# board-scope-R3.net
KiCad netlist of a schematic drawn in EAGLE
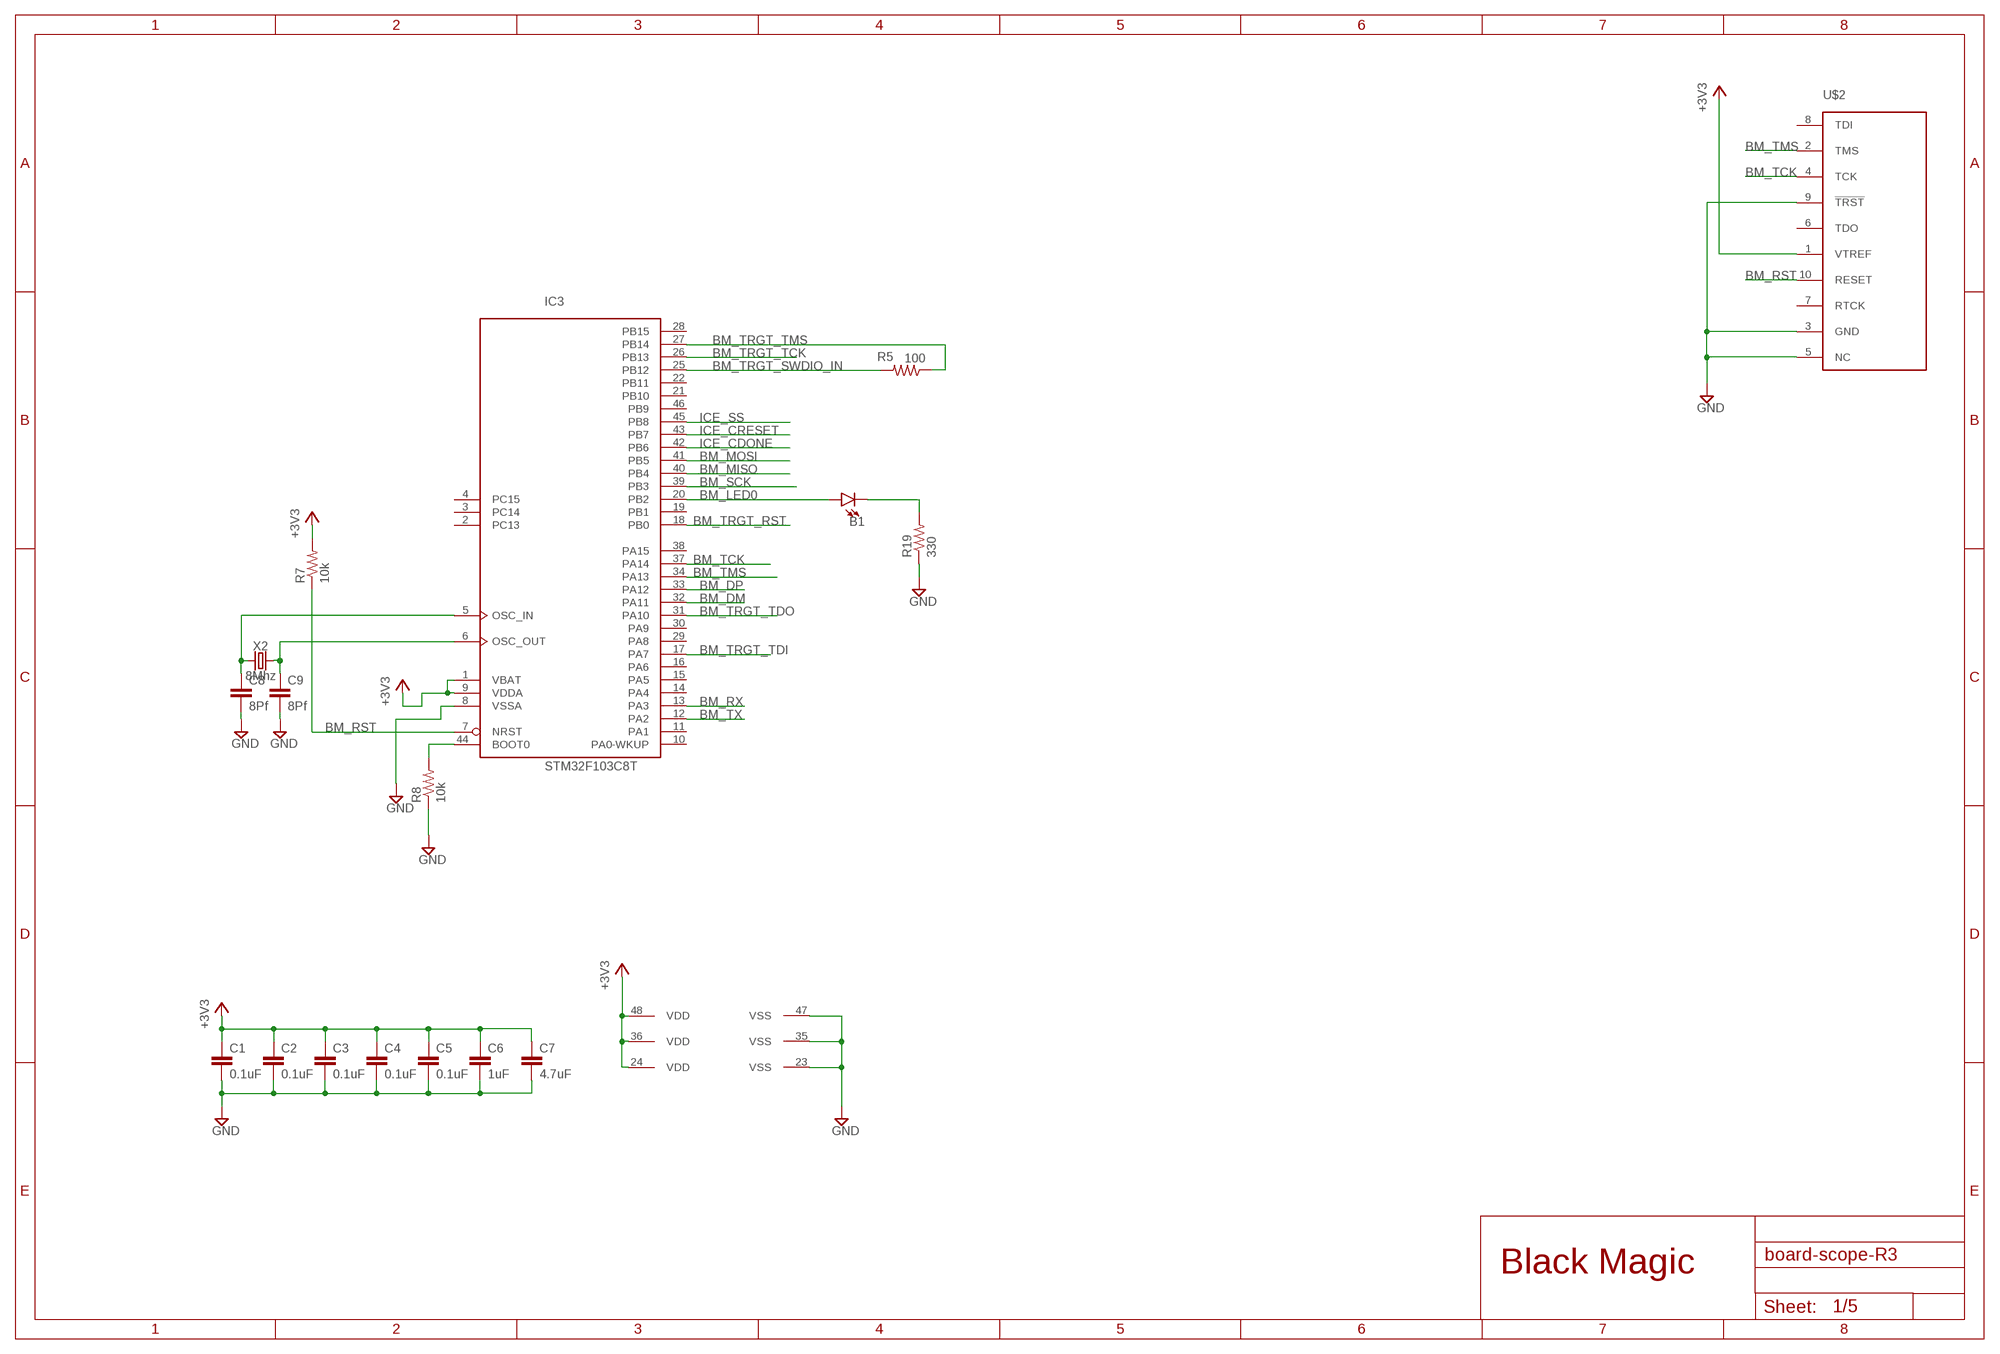
[diagram p0: schematic, sheet 1]
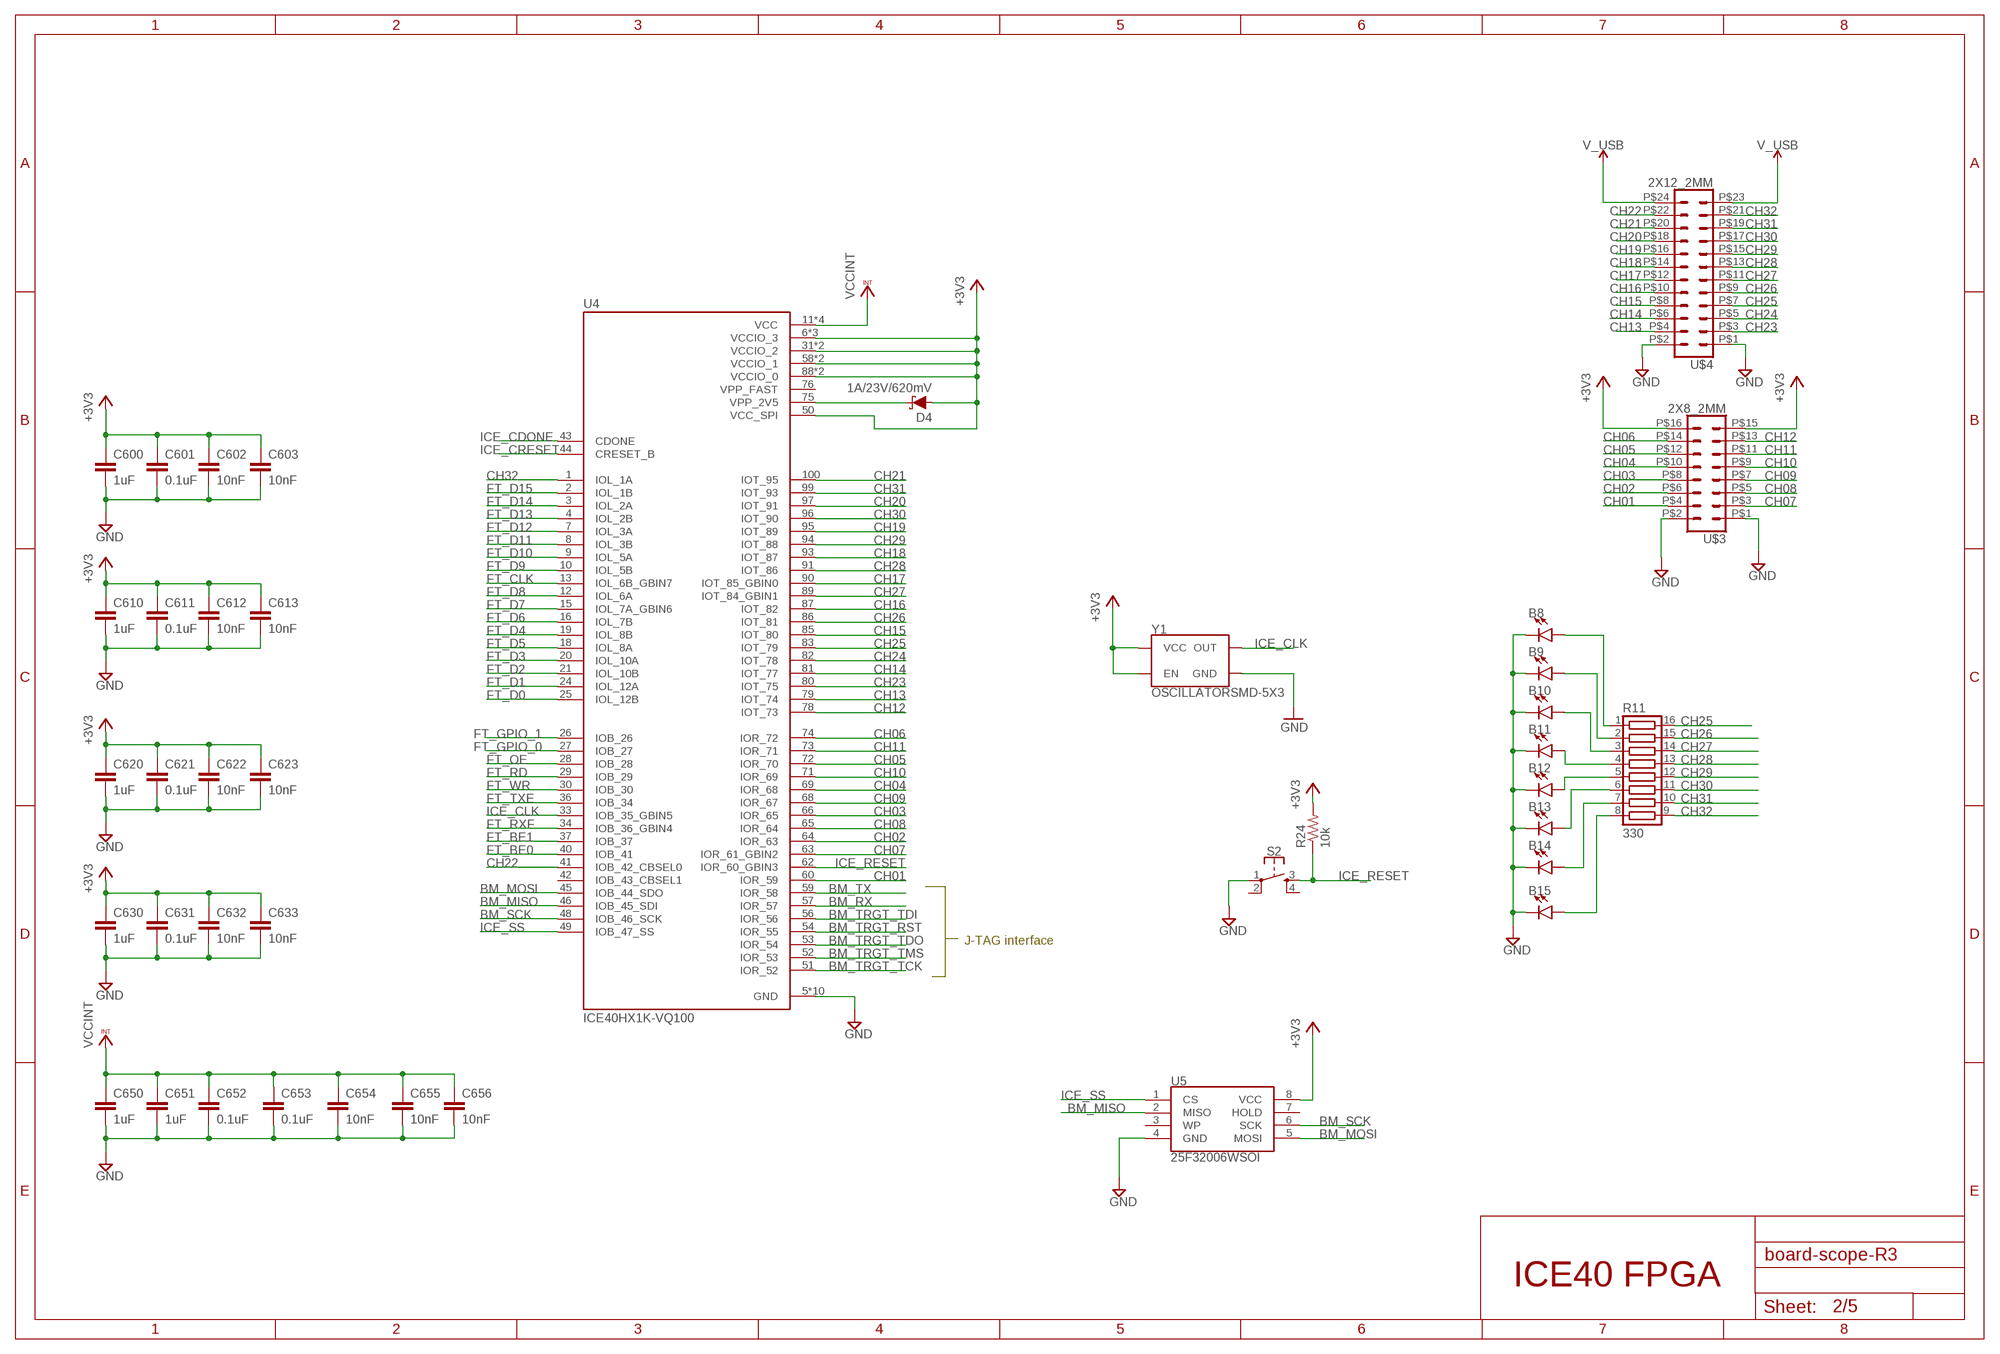
[diagram p1: schematic, sheet 2]
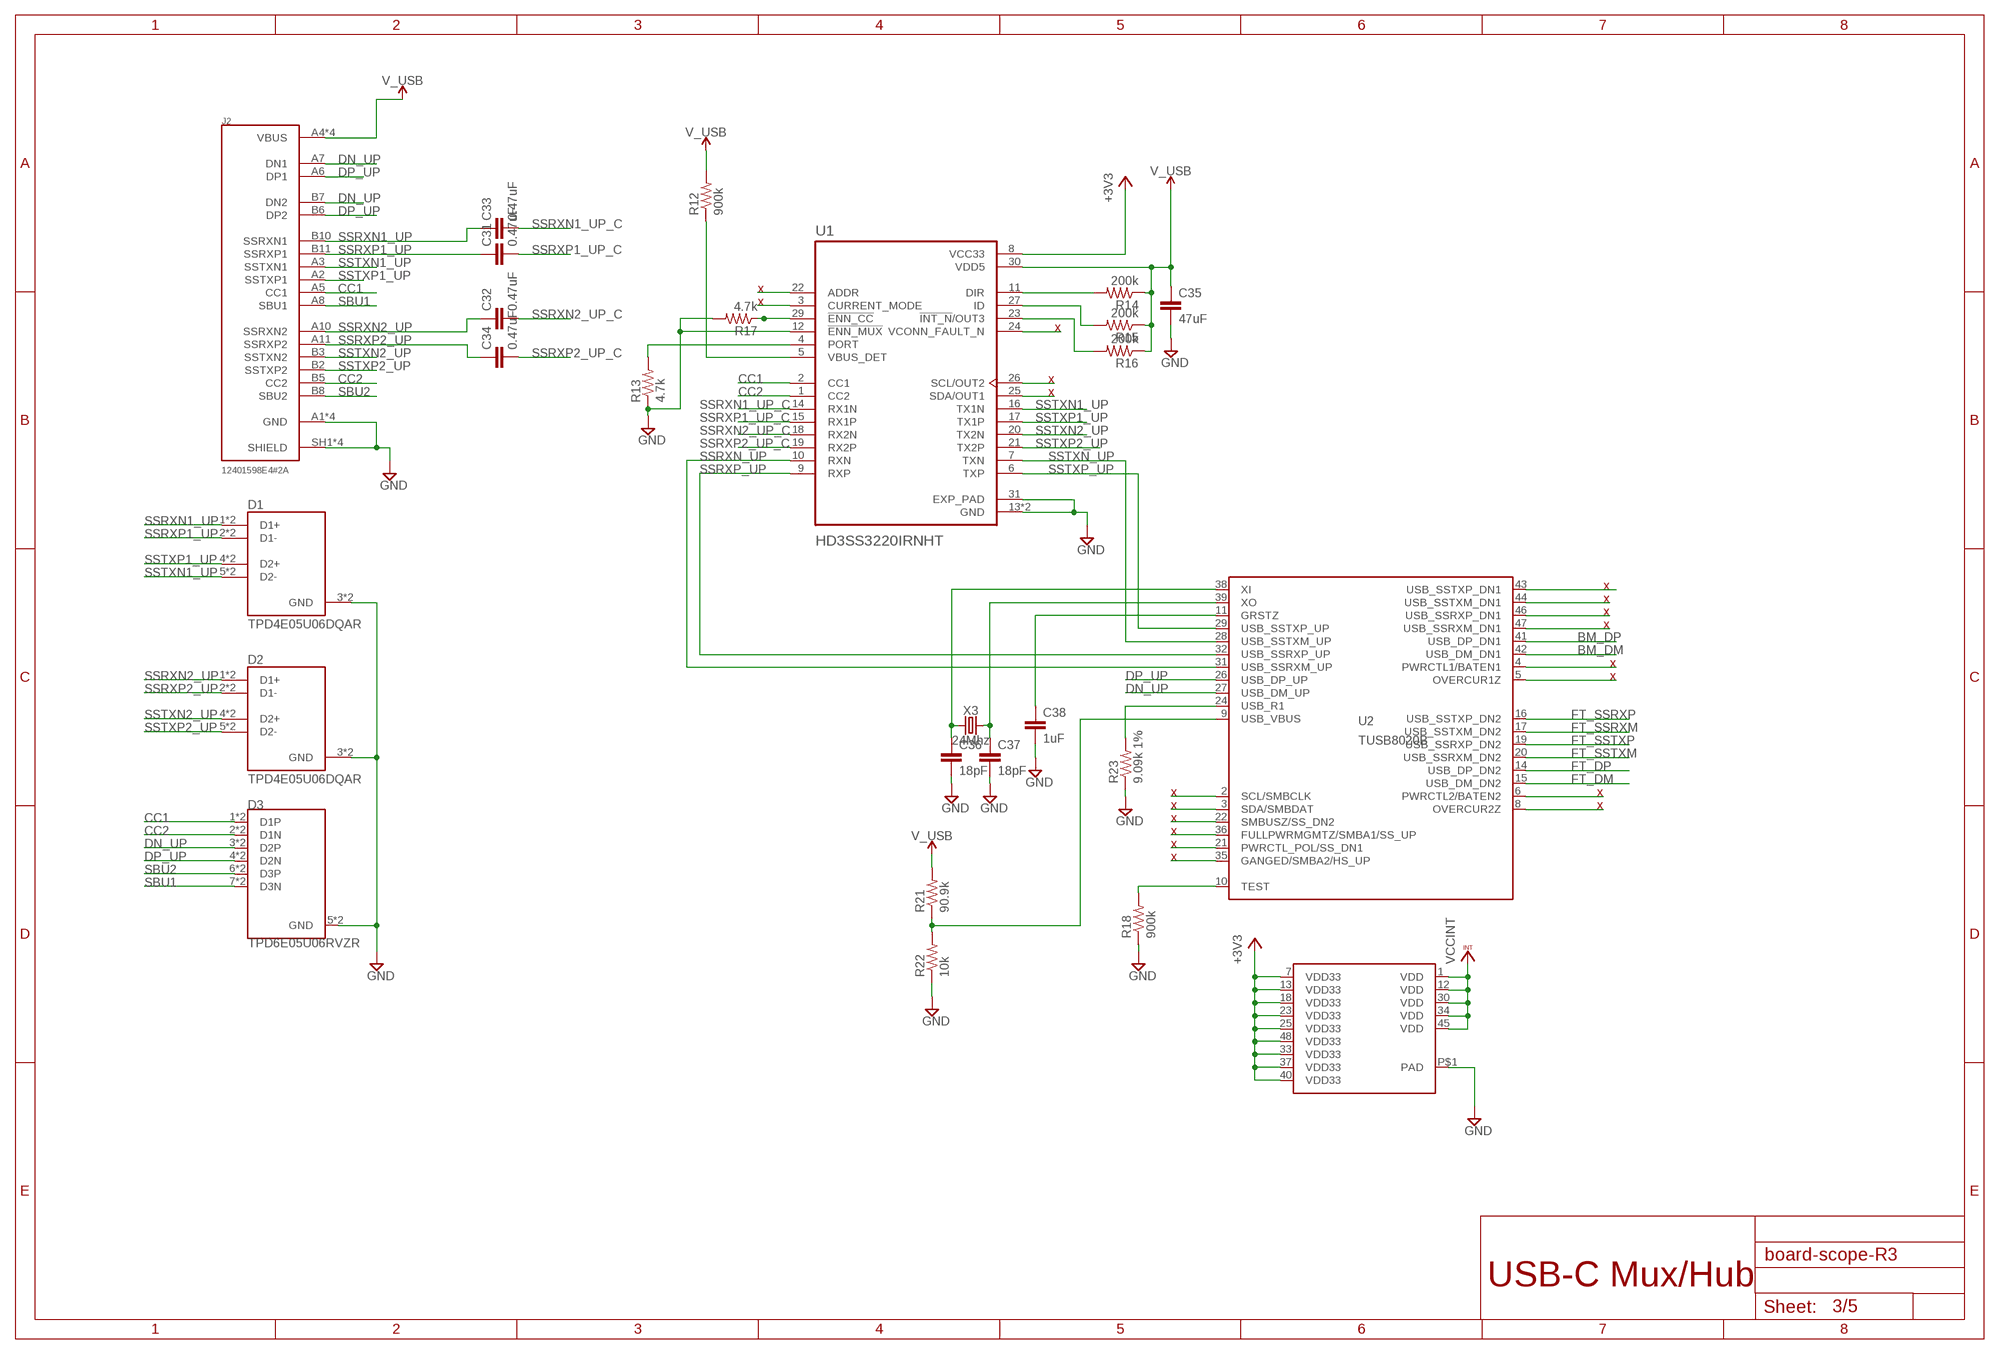
[diagram p2: schematic, sheet 3]
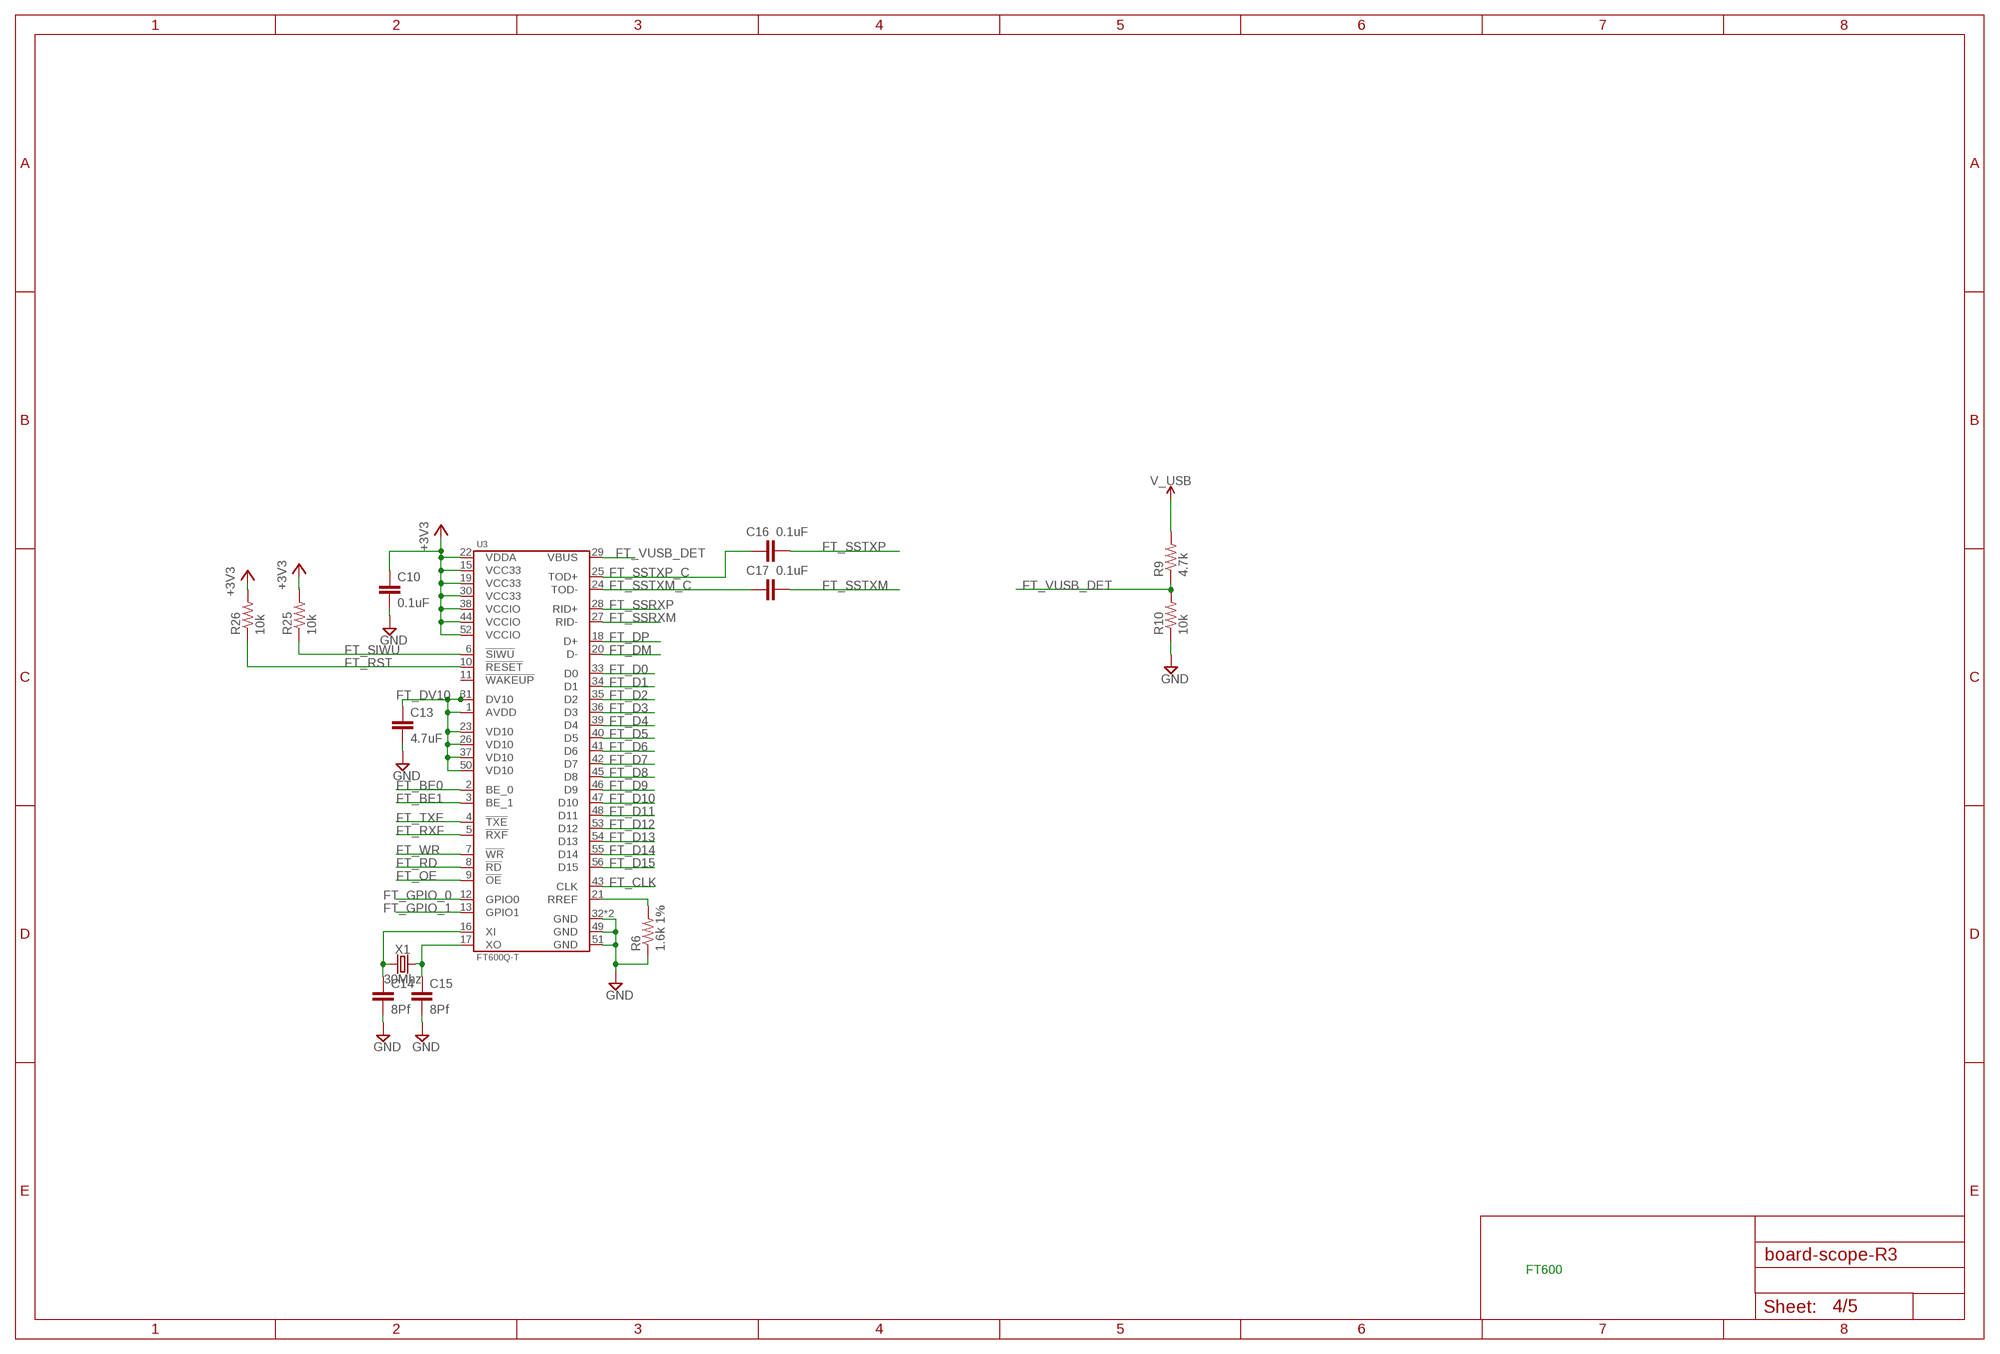
[diagram p3: schematic, sheet 4]
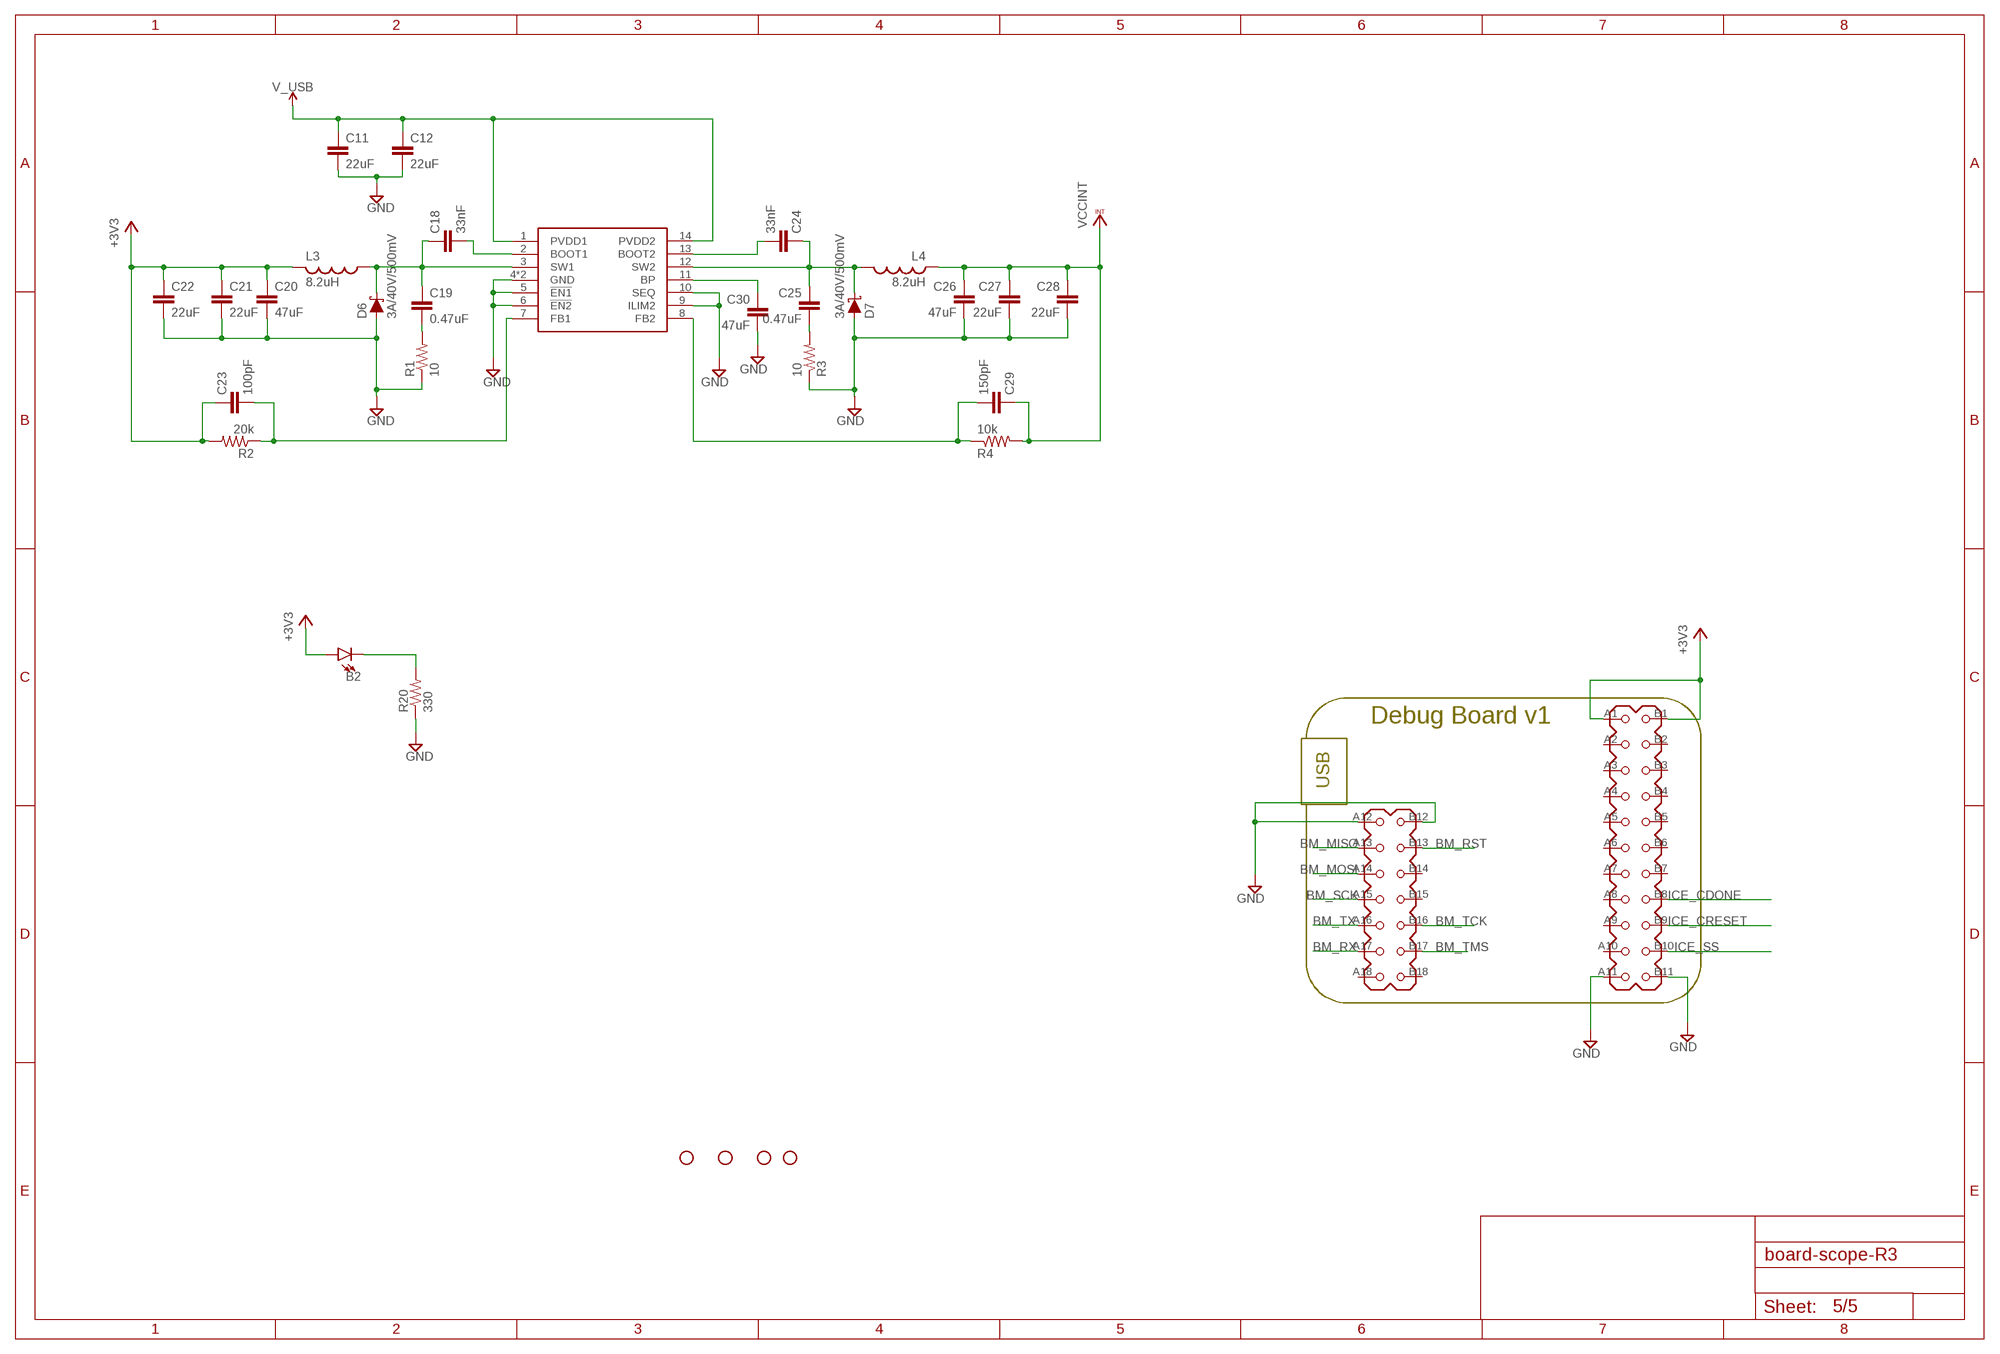
[diagram p4: schematic, sheet 5]

(export (version "E")
  (design (tool "Eeschema 10.0.6"))
  (components
    (comp (ref "C10")
      (value "0.1uF")
      (footprint "eagle-import:C0603K")
      (libsource (lib "eagle-import") (part "C-EUC0603K"))
    )
    (comp (ref "C13")
      (value "4.7uF")
      (footprint "eagle-import:C0603K")
      (libsource (lib "eagle-import") (part "C-EUC0603K"))
    )
    (comp (ref "C14")
      (value "8Pf")
      (footprint "eagle-import:C0603K")
      (libsource (lib "eagle-import") (part "C-EUC0603K"))
    )
    (comp (ref "C15")
      (value "8Pf")
      (footprint "eagle-import:C0603K")
      (libsource (lib "eagle-import") (part "C-EUC0603K"))
    )
    (comp (ref "C16")
      (value "0.1uF")
      (footprint "eagle-import:C0603K")
      (libsource (lib "eagle-import") (part "C-EUC0603K"))
    )
    (comp (ref "C17")
      (value "0.1uF")
      (footprint "eagle-import:C0603K")
      (libsource (lib "eagle-import") (part "C-EUC0603K"))
    )
    (comp (ref "R6")
      (value "1.6k 1%")
      (footprint "eagle-import:R0603")
      (libsource (lib "eagle-import") (part "R-US_R0603"))
    )
    (comp (ref "R9")
      (value "4.7k")
      (footprint "eagle-import:R0603")
      (libsource (lib "eagle-import") (part "R-US_R0603"))
    )
    (comp (ref "R10")
      (value "10k")
      (footprint "eagle-import:R0603")
      (libsource (lib "eagle-import") (part "R-US_R0603"))
    )
    (comp (ref "R25")
      (value "10k")
      (footprint "eagle-import:R0603")
      (libsource (lib "eagle-import") (part "R-US_R0603"))
    )
    (comp (ref "R26")
      (value "10k")
      (footprint "eagle-import:R0603")
      (libsource (lib "eagle-import") (part "R-US_R0603"))
    )
    (comp (ref "U3")
      (value "FT600Q-T")
      (footprint "eagle-import:VQFN-56-7MM")
      (libsource (lib "eagle-import") (part "FT600Q-T"))
    )
    (comp (ref "X1")
      (value "30Mhz")
      (footprint "eagle-import:CRYSTAL-SMD-5X3.2-4PAD")
      (libsource (lib "eagle-import") (part "CRYSTALSMD-5X3.2-4PAD"))
    )
    (comp (ref "B2")
      (value "LED0603")
      (footprint "eagle-import:LED-0603")
      (libsource (lib "eagle-import") (part "LED0603"))
    )
    (comp (ref "C11")
      (value "22uF")
      (footprint "eagle-import:C0603K")
      (libsource (lib "eagle-import") (part "C-EUC0603K"))
    )
    (comp (ref "C12")
      (value "22uF")
      (footprint "eagle-import:C0603K")
      (libsource (lib "eagle-import") (part "C-EUC0603K"))
    )
    (comp (ref "C18")
      (value "33nF")
      (footprint "eagle-import:C0603K")
      (libsource (lib "eagle-import") (part "C-EUC0603K"))
    )
    (comp (ref "C19")
      (value "0.47uF")
      (footprint "eagle-import:C0603K")
      (libsource (lib "eagle-import") (part "C-EUC0603K"))
    )
    (comp (ref "C20")
      (value "47uF")
      (footprint "eagle-import:C0603K")
      (libsource (lib "eagle-import") (part "C-EUC0603K"))
    )
    (comp (ref "C21")
      (value "22uF")
      (footprint "eagle-import:C0603K")
      (libsource (lib "eagle-import") (part "C-EUC0603K"))
    )
    (comp (ref "C22")
      (value "22uF")
      (footprint "eagle-import:C0603K")
      (libsource (lib "eagle-import") (part "C-EUC0603K"))
    )
    (comp (ref "C23")
      (value "100pF")
      (footprint "eagle-import:C0603K")
      (libsource (lib "eagle-import") (part "C-EUC0603K"))
    )
    (comp (ref "C24")
      (value "33nF")
      (footprint "eagle-import:C0603K")
      (libsource (lib "eagle-import") (part "C-EUC0603K"))
    )
    (comp (ref "C25")
      (value "0.47uF")
      (footprint "eagle-import:C0603K")
      (libsource (lib "eagle-import") (part "C-EUC0603K"))
    )
    (comp (ref "C26")
      (value "47uF")
      (footprint "eagle-import:C0603K")
      (libsource (lib "eagle-import") (part "C-EUC0603K"))
    )
    (comp (ref "C27")
      (value "22uF")
      (footprint "eagle-import:C0603K")
      (libsource (lib "eagle-import") (part "C-EUC0603K"))
    )
    (comp (ref "C28")
      (value "22uF")
      (footprint "eagle-import:C0603K")
      (libsource (lib "eagle-import") (part "C-EUC0603K"))
    )
    (comp (ref "C29")
      (value "150pF")
      (footprint "eagle-import:C0603K")
      (libsource (lib "eagle-import") (part "C-EUC0603K"))
    )
    (comp (ref "C30")
      (value "47uF")
      (footprint "eagle-import:C0603K")
      (libsource (lib "eagle-import") (part "C-EUC0603K"))
    )
    (comp (ref "D6")
      (value "3A/40V/500mV")
      (footprint "eagle-import:SMA-DIODE")
      (libsource (lib "eagle-import") (part "DIODE-SCHOTTKY-B340A"))
    )
    (comp (ref "D7")
      (value "3A/40V/500mV")
      (footprint "eagle-import:SMA-DIODE")
      (libsource (lib "eagle-import") (part "DIODE-SCHOTTKY-B340A"))
    )
    (comp (ref "H1")
      (value "STAND-OFF")
      (footprint "eagle-import:STAND-OFF")
      (libsource (lib "eagle-import") (part "STAND-OFF"))
    )
    (comp (ref "H2")
      (value "STAND-OFF")
      (footprint "eagle-import:STAND-OFF")
      (libsource (lib "eagle-import") (part "STAND-OFF"))
    )
    (comp (ref "H3")
      (value "STAND-OFF")
      (footprint "eagle-import:STAND-OFF")
      (libsource (lib "eagle-import") (part "STAND-OFF"))
    )
    (comp (ref "H4")
      (value "STAND-OFF")
      (footprint "eagle-import:STAND-OFF")
      (libsource (lib "eagle-import") (part "STAND-OFF"))
    )
    (comp (ref "L3")
      (value "8.2uH")
      (footprint "eagle-import:L5650M")
      (libsource (lib "eagle-import") (part "L-USL5650M"))
    )
    (comp (ref "L4")
      (value "8.2uH")
      (footprint "eagle-import:L5650M")
      (libsource (lib "eagle-import") (part "L-USL5650M"))
    )
    (comp (ref "R1")
      (value "10")
      (footprint "eagle-import:R0603")
      (libsource (lib "eagle-import") (part "R-US_R0603"))
    )
    (comp (ref "R2")
      (value "20k")
      (footprint "eagle-import:R0603")
      (libsource (lib "eagle-import") (part "R-US_R0603"))
    )
    (comp (ref "R3")
      (value "10")
      (footprint "eagle-import:R0603")
      (libsource (lib "eagle-import") (part "R-US_R0603"))
    )
    (comp (ref "R4")
      (value "10k")
      (footprint "eagle-import:R0603")
      (libsource (lib "eagle-import") (part "R-US_R0603"))
    )
    (comp (ref "R20")
      (value "330")
      (footprint "eagle-import:R0603")
      (libsource (lib "eagle-import") (part "R-US_R0603"))
    )
    (comp (ref "U$1")
      (value "EDGE_DEBUG")
      (footprint "eagle-import:PCI-E_36_EDGE_MID")
      (libsource (lib "eagle-import") (part "EDGE_DEBUG"))
    )
    (comp (ref "U7")
      (value "TPS54386")
      (footprint "eagle-import:HTSSOP14PWP")
      (libsource (lib "eagle-import") (part "TPS54386"))
    )
    (comp (ref "B1")
      (value "LED0603")
      (footprint "eagle-import:LED-0603")
      (libsource (lib "eagle-import") (part "LED0603"))
    )
    (comp (ref "C1")
      (value "0.1uF")
      (footprint "eagle-import:C0603K")
      (libsource (lib "eagle-import") (part "C-EUC0603K"))
    )
    (comp (ref "C2")
      (value "0.1uF")
      (footprint "eagle-import:C0603K")
      (libsource (lib "eagle-import") (part "C-EUC0603K"))
    )
    (comp (ref "C3")
      (value "0.1uF")
      (footprint "eagle-import:C0603K")
      (libsource (lib "eagle-import") (part "C-EUC0603K"))
    )
    (comp (ref "C4")
      (value "0.1uF")
      (footprint "eagle-import:C0603K")
      (libsource (lib "eagle-import") (part "C-EUC0603K"))
    )
    (comp (ref "C5")
      (value "0.1uF")
      (footprint "eagle-import:C0603K")
      (libsource (lib "eagle-import") (part "C-EUC0603K"))
    )
    (comp (ref "C6")
      (value "1uF")
      (footprint "eagle-import:C0603K")
      (libsource (lib "eagle-import") (part "C-EUC0603K"))
    )
    (comp (ref "C7")
      (value "4.7uF")
      (footprint "eagle-import:C0603K")
      (libsource (lib "eagle-import") (part "C-EUC0603K"))
    )
    (comp (ref "C8")
      (value "8Pf")
      (footprint "eagle-import:C0603K")
      (libsource (lib "eagle-import") (part "C-EUC0603K"))
    )
    (comp (ref "C9")
      (value "8Pf")
      (footprint "eagle-import:C0603K")
      (libsource (lib "eagle-import") (part "C-EUC0603K"))
    )
    (comp (ref "IC3")
      (value "STM32F103C8T")
      (footprint "eagle-import:LQFP48")
      (libsource (lib "eagle-import") (part "STM32F103CT8"))
    )
    (comp (ref "R5")
      (value "100")
      (footprint "eagle-import:R0603")
      (libsource (lib "eagle-import") (part "R-US_R0603"))
    )
    (comp (ref "R7")
      (value "10k")
      (footprint "eagle-import:R0603")
      (libsource (lib "eagle-import") (part "R-US_R0603"))
    )
    (comp (ref "R8")
      (value "10k")
      (footprint "eagle-import:R0603")
      (libsource (lib "eagle-import") (part "R-US_R0603"))
    )
    (comp (ref "R19")
      (value "330")
      (footprint "eagle-import:R0603")
      (libsource (lib "eagle-import") (part "R-US_R0603"))
    )
    (comp (ref "U$2")
      (value "TC2050-NL-MCP-NL")
      (footprint "eagle-import:TC2030-MCP-NL")
      (libsource (lib "eagle-import") (part "TC2050-NL-MCP-NL"))
    )
    (comp (ref "X2")
      (value "8Mhz")
      (footprint "eagle-import:CRYSTAL-SMD-5X3.2-4PAD")
      (libsource (lib "eagle-import") (part "CRYSTALSMD-5X3.2-4PAD"))
    )
    (comp (ref "C31")
      (value "0.47uF")
      (footprint "eagle-import:C0603K")
      (libsource (lib "eagle-import") (part "C-EUC0603K"))
    )
    (comp (ref "C32")
      (value "0.47uF")
      (footprint "eagle-import:C0603K")
      (libsource (lib "eagle-import") (part "C-EUC0603K"))
    )
    (comp (ref "C33")
      (value "0.47uF")
      (footprint "eagle-import:C0603K")
      (libsource (lib "eagle-import") (part "C-EUC0603K"))
    )
    (comp (ref "C34")
      (value "0.47uF")
      (footprint "eagle-import:C0603K")
      (libsource (lib "eagle-import") (part "C-EUC0603K"))
    )
    (comp (ref "C35")
      (value "47uF")
      (footprint "eagle-import:C0603K")
      (libsource (lib "eagle-import") (part "C-EUC0603K"))
    )
    (comp (ref "C36")
      (value "18pF")
      (footprint "eagle-import:C0603K")
      (libsource (lib "eagle-import") (part "C-EUC0603K"))
    )
    (comp (ref "C37")
      (value "18pF")
      (footprint "eagle-import:C0603K")
      (libsource (lib "eagle-import") (part "C-EUC0603K"))
    )
    (comp (ref "C38")
      (value "1uF")
      (footprint "eagle-import:C0603K")
      (libsource (lib "eagle-import") (part "C-EUC0603K"))
    )
    (comp (ref "D1")
      (value "TPD4E05U06DQAR")
      (footprint "eagle-import:TI_TPD4E05U06DQAR")
      (fields (field (name "MANUFACTURER") "Texas Instruments"))
      (libsource (lib "eagle-import") (part "TPD4E05U06DQAR"))
    )
    (comp (ref "D2")
      (value "TPD4E05U06DQAR")
      (footprint "eagle-import:TI_TPD4E05U06DQAR")
      (fields (field (name "MANUFACTURER") "Texas Instruments"))
      (libsource (lib "eagle-import") (part "TPD4E05U06DQAR"))
    )
    (comp (ref "D3")
      (value "TPD6E05U06RVZR")
      (footprint "eagle-import:SON50P135X350X55-14N")
      (fields (field (name "MANUFACTURER") "Texas Instruments"))
      (libsource (lib "eagle-import") (part "TPD6E05U06RVZR"))
    )
    (comp (ref "J2")
      (value "12401598E4#2A")
      (footprint "eagle-import:AMPHENOL_12401598E4#2A")
      (fields (field (name "MF") "Amphenol ICC"))
      (libsource (lib "eagle-import") (part "12401598E4#2A"))
    )
    (comp (ref "R12")
      (value "900k")
      (footprint "eagle-import:R0603")
      (libsource (lib "eagle-import") (part "R-US_R0603"))
    )
    (comp (ref "R13")
      (value "4.7k")
      (footprint "eagle-import:R0603")
      (libsource (lib "eagle-import") (part "R-US_R0603"))
    )
    (comp (ref "R14")
      (value "200k")
      (footprint "eagle-import:R0603")
      (libsource (lib "eagle-import") (part "R-US_R0603"))
    )
    (comp (ref "R15")
      (value "200k")
      (footprint "eagle-import:R0603")
      (libsource (lib "eagle-import") (part "R-US_R0603"))
    )
    (comp (ref "R16")
      (value "200k")
      (footprint "eagle-import:R0603")
      (libsource (lib "eagle-import") (part "R-US_R0603"))
    )
    (comp (ref "R17")
      (value "4.7k")
      (footprint "eagle-import:R0603")
      (libsource (lib "eagle-import") (part "R-US_R0603"))
    )
    (comp (ref "R18")
      (value "900k")
      (footprint "eagle-import:R0603")
      (libsource (lib "eagle-import") (part "R-US_R0603"))
    )
    (comp (ref "R21")
      (value "90.9k")
      (footprint "eagle-import:R0603")
      (libsource (lib "eagle-import") (part "R-US_R0603"))
    )
    (comp (ref "R22")
      (value "10k")
      (footprint "eagle-import:R0603")
      (libsource (lib "eagle-import") (part "R-US_R0603"))
    )
    (comp (ref "R23")
      (value "9.09k 1%")
      (footprint "eagle-import:R0603")
      (libsource (lib "eagle-import") (part "R-US_R0603"))
    )
    (comp (ref "U1")
      (value "HD3SS3220IRNHT")
      (footprint "eagle-import:QFN40P450X250X80-31N120X320")
      (fields (field (name "MF") "Texas Instruments"))
      (libsource (lib "eagle-import") (part "HD3SS3220IRNHT"))
    )
    (comp (ref "U2")
      (value "TUSB8020B")
      (footprint "eagle-import:TQFP48")
      (libsource (lib "eagle-import") (part "TUSB8020B"))
    )
    (comp (ref "X3")
      (value "24Mhz")
      (footprint "eagle-import:CRYSTAL-SMD-5X3.2-4PAD")
      (libsource (lib "eagle-import") (part "CRYSTALSMD-5X3.2-4PAD"))
    )
    (comp (ref "B8")
      (value "LED0603")
      (footprint "eagle-import:LED-0603")
      (libsource (lib "eagle-import") (part "LED0603"))
    )
    (comp (ref "B9")
      (value "LED0603")
      (footprint "eagle-import:LED-0603")
      (libsource (lib "eagle-import") (part "LED0603"))
    )
    (comp (ref "B10")
      (value "LED0603")
      (footprint "eagle-import:LED-0603")
      (libsource (lib "eagle-import") (part "LED0603"))
    )
    (comp (ref "B11")
      (value "LED0603")
      (footprint "eagle-import:LED-0603")
      (libsource (lib "eagle-import") (part "LED0603"))
    )
    (comp (ref "B12")
      (value "LED0603")
      (footprint "eagle-import:LED-0603")
      (libsource (lib "eagle-import") (part "LED0603"))
    )
    (comp (ref "B13")
      (value "LED0603")
      (footprint "eagle-import:LED-0603")
      (libsource (lib "eagle-import") (part "LED0603"))
    )
    (comp (ref "B14")
      (value "LED0603")
      (footprint "eagle-import:LED-0603")
      (libsource (lib "eagle-import") (part "LED0603"))
    )
    (comp (ref "B15")
      (value "LED0603")
      (footprint "eagle-import:LED-0603")
      (libsource (lib "eagle-import") (part "LED0603"))
    )
    (comp (ref "C600")
      (value "1uF")
      (footprint "eagle-import:C0603K")
      (libsource (lib "eagle-import") (part "C-EUC0603K"))
    )
    (comp (ref "C601")
      (value "0.1uF")
      (footprint "eagle-import:C0603K")
      (libsource (lib "eagle-import") (part "C-EUC0603K"))
    )
    (comp (ref "C602")
      (value "10nF")
      (footprint "eagle-import:C0603K")
      (libsource (lib "eagle-import") (part "C-EUC0603K"))
    )
    (comp (ref "C603")
      (value "10nF")
      (footprint "eagle-import:C0603K")
      (libsource (lib "eagle-import") (part "C-EUC0603K"))
    )
    (comp (ref "C610")
      (value "1uF")
      (footprint "eagle-import:C0603K")
      (libsource (lib "eagle-import") (part "C-EUC0603K"))
    )
    (comp (ref "C611")
      (value "0.1uF")
      (footprint "eagle-import:C0603K")
      (libsource (lib "eagle-import") (part "C-EUC0603K"))
    )
    (comp (ref "C612")
      (value "10nF")
      (footprint "eagle-import:C0603K")
      (libsource (lib "eagle-import") (part "C-EUC0603K"))
    )
    (comp (ref "C613")
      (value "10nF")
      (footprint "eagle-import:C0603K")
      (libsource (lib "eagle-import") (part "C-EUC0603K"))
    )
    (comp (ref "C620")
      (value "1uF")
      (footprint "eagle-import:C0603K")
      (libsource (lib "eagle-import") (part "C-EUC0603K"))
    )
    (comp (ref "C621")
      (value "0.1uF")
      (footprint "eagle-import:C0603K")
      (libsource (lib "eagle-import") (part "C-EUC0603K"))
    )
    (comp (ref "C622")
      (value "10nF")
      (footprint "eagle-import:C0603K")
      (libsource (lib "eagle-import") (part "C-EUC0603K"))
    )
    (comp (ref "C623")
      (value "10nF")
      (footprint "eagle-import:C0603K")
      (libsource (lib "eagle-import") (part "C-EUC0603K"))
    )
    (comp (ref "C630")
      (value "1uF")
      (footprint "eagle-import:C0603K")
      (libsource (lib "eagle-import") (part "C-EUC0603K"))
    )
    (comp (ref "C631")
      (value "0.1uF")
      (footprint "eagle-import:C0603K")
      (libsource (lib "eagle-import") (part "C-EUC0603K"))
    )
    (comp (ref "C632")
      (value "10nF")
      (footprint "eagle-import:C0603K")
      (libsource (lib "eagle-import") (part "C-EUC0603K"))
    )
    (comp (ref "C633")
      (value "10nF")
      (footprint "eagle-import:C0603K")
      (libsource (lib "eagle-import") (part "C-EUC0603K"))
    )
    (comp (ref "C650")
      (value "1uF")
      (footprint "eagle-import:C0603K")
      (libsource (lib "eagle-import") (part "C-EUC0603K"))
    )
    (comp (ref "C651")
      (value "1uF")
      (footprint "eagle-import:C0603K")
      (libsource (lib "eagle-import") (part "C-EUC0603K"))
    )
    (comp (ref "C652")
      (value "0.1uF")
      (footprint "eagle-import:C0603K")
      (libsource (lib "eagle-import") (part "C-EUC0603K"))
    )
    (comp (ref "C653")
      (value "0.1uF")
      (footprint "eagle-import:C0603K")
      (libsource (lib "eagle-import") (part "C-EUC0603K"))
    )
    (comp (ref "C654")
      (value "10nF")
      (footprint "eagle-import:C0603K")
      (libsource (lib "eagle-import") (part "C-EUC0603K"))
    )
    (comp (ref "C655")
      (value "10nF")
      (footprint "eagle-import:C0603K")
      (libsource (lib "eagle-import") (part "C-EUC0603K"))
    )
    (comp (ref "C656")
      (value "10nF")
      (footprint "eagle-import:C0603K")
      (libsource (lib "eagle-import") (part "C-EUC0603K"))
    )
    (comp (ref "D4")
      (value "1A/23V/620mV")
      (footprint "eagle-import:SOD-323")
      (libsource (lib "eagle-import") (part "DIODE-SCHOTTKY-BAT20J"))
    )
    (comp (ref "R11")
      (value "330")
      (footprint "eagle-import:CTS743C163")
      (libsource (lib "eagle-import") (part "CTS742C163"))
    )
    (comp (ref "R24")
      (value "10k")
      (footprint "eagle-import:R0603")
      (libsource (lib "eagle-import") (part "R-US_R0603"))
    )
    (comp (ref "S2")
      (value "MOMENTARY-SWITCH-SPST-2-SMD-5.2MM")
      (footprint "eagle-import:TACTILE_SWITCH_SMD_5.2MM")
      (libsource (lib "eagle-import") (part "MOMENTARY-SWITCH-SPST-2-SMD-5.2MM"))
    )
    (comp (ref "U$3")
      (value "2X8_2MM")
      (footprint "eagle-import:2X8_2MM")
      (libsource (lib "eagle-import") (part "2X8_2MM"))
    )
    (comp (ref "U$4")
      (value "2X12_2MM")
      (footprint "eagle-import:2X12_2MM")
      (libsource (lib "eagle-import") (part "2X12_2MM"))
    )
    (comp (ref "U4")
      (value "ICE40HX1K-VQ100")
      (footprint "eagle-import:QFP50P1600X1600X120-100N")
      (fields (field (name "MF") "Lattice Semiconductor"))
      (libsource (lib "eagle-import") (part "ICE40HX1K-VQ100"))
    )
    (comp (ref "U5")
      (value "25F32006WSOI")
      (footprint "eagle-import:SO08-EIAJ")
      (libsource (lib "eagle-import") (part "SPI_FLASH-X25XXSMD1"))
    )
    (comp (ref "Y1")
      (value "OSCILLATORSMD-5X3")
      (footprint "eagle-import:OSCILLATOR-SMD-5X3.2")
      (libsource (lib "eagle-import") (part "OSCILLATORSMD-5X3"))
    )
  )
  (nets
    (net (code "1") (name "+3V3") (class "Default")
      (node (ref "B2") (pin "A") (pinfunction "A_A") (pintype "passive"))
      (node (ref "C1") (pin "1") (pinfunction "1_1") (pintype "passive"))
      (node (ref "C10") (pin "1") (pinfunction "1_1") (pintype "passive"))
      (node (ref "C2") (pin "1") (pinfunction "1_1") (pintype "passive"))
      (node (ref "C20") (pin "1") (pinfunction "1_1") (pintype "passive"))
      (node (ref "C21") (pin "1") (pinfunction "1_1") (pintype "passive"))
      (node (ref "C22") (pin "1") (pinfunction "1_1") (pintype "passive"))
      (node (ref "C23") (pin "1") (pinfunction "1_1") (pintype "passive"))
      (node (ref "C3") (pin "1") (pinfunction "1_1") (pintype "passive"))
      (node (ref "C4") (pin "1") (pinfunction "1_1") (pintype "passive"))
      (node (ref "C5") (pin "1") (pinfunction "1_1") (pintype "passive"))
      (node (ref "C6") (pin "1") (pinfunction "1_1") (pintype "passive"))
      (node (ref "C600") (pin "1") (pinfunction "1_1") (pintype "passive"))
      (node (ref "C601") (pin "1") (pinfunction "1_1") (pintype "passive"))
      (node (ref "C602") (pin "1") (pinfunction "1_1") (pintype "passive"))
      (node (ref "C603") (pin "1") (pinfunction "1_1") (pintype "passive"))
      (node (ref "C610") (pin "1") (pinfunction "1_1") (pintype "passive"))
      (node (ref "C611") (pin "1") (pinfunction "1_1") (pintype "passive"))
      (node (ref "C612") (pin "1") (pinfunction "1_1") (pintype "passive"))
      (node (ref "C613") (pin "1") (pinfunction "1_1") (pintype "passive"))
      (node (ref "C620") (pin "1") (pinfunction "1_1") (pintype "passive"))
      (node (ref "C621") (pin "1") (pinfunction "1_1") (pintype "passive"))
      (node (ref "C622") (pin "1") (pinfunction "1_1") (pintype "passive"))
      (node (ref "C623") (pin "1") (pinfunction "1_1") (pintype "passive"))
      (node (ref "C630") (pin "1") (pinfunction "1_1") (pintype "passive"))
      (node (ref "C631") (pin "1") (pinfunction "1_1") (pintype "passive"))
      (node (ref "C632") (pin "1") (pinfunction "1_1") (pintype "passive"))
      (node (ref "C633") (pin "1") (pinfunction "1_1") (pintype "passive"))
      (node (ref "C7") (pin "1") (pinfunction "1_1") (pintype "passive"))
      (node (ref "D4") (pin "A") (pinfunction "A_A") (pintype "passive"))
      (node (ref "IC3") (pin "1") (pinfunction "VBAT_1") (pintype "power_in"))
      (node (ref "IC3") (pin "24") (pinfunction "VDD_24") (pintype "power_in"))
      (node (ref "IC3") (pin "36") (pinfunction "VDD_36") (pintype "power_in"))
      (node (ref "IC3") (pin "48") (pinfunction "VDD_48") (pintype "power_in"))
      (node (ref "IC3") (pin "9") (pinfunction "VDDA_9") (pintype "power_in"))
      (node (ref "L3") (pin "2") (pinfunction "2_2") (pintype "passive"))
      (node (ref "R2") (pin "2") (pinfunction "2_2") (pintype "passive"))
      (node (ref "R24") (pin "2") (pinfunction "2_2") (pintype "passive"))
      (node (ref "R25") (pin "2") (pinfunction "2_2") (pintype "passive"))
      (node (ref "R26") (pin "2") (pinfunction "2_2") (pintype "passive"))
      (node (ref "R7") (pin "2") (pinfunction "2_2") (pintype "passive"))
      (node (ref "U$1") (pin "A1") (pinfunction "A1_A1") (pintype "bidirectional"))
      (node (ref "U$1") (pin "B1") (pinfunction "B1_B1") (pintype "bidirectional"))
      (node (ref "U$2") (pin "1") (pinfunction "VTREF_1") (pintype "bidirectional"))
      (node (ref "U$3") (pin "P$15") (pinfunction "15_P$15") (pintype "passive"))
      (node (ref "U$3") (pin "P$16") (pinfunction "16_P$16") (pintype "passive"))
      (node (ref "U1") (pin "8") (pinfunction "VCC33_8") (pintype "power_in"))
      (node (ref "U2") (pin "13") (pinfunction "VDD33_13") (pintype "bidirectional"))
      (node (ref "U2") (pin "18") (pinfunction "VDD33_18") (pintype "bidirectional"))
      (node (ref "U2") (pin "23") (pinfunction "VDD33_23") (pintype "bidirectional"))
      (node (ref "U2") (pin "25") (pinfunction "VDD33_25") (pintype "bidirectional"))
      (node (ref "U2") (pin "33") (pinfunction "VDD33_33") (pintype "bidirectional"))
      (node (ref "U2") (pin "37") (pinfunction "VDD33_37") (pintype "bidirectional"))
      (node (ref "U2") (pin "40") (pinfunction "VDD33_40") (pintype "bidirectional"))
      (node (ref "U2") (pin "48") (pinfunction "VDD33_48") (pintype "bidirectional"))
      (node (ref "U2") (pin "7") (pinfunction "VDD33_7") (pintype "power_in"))
      (node (ref "U3") (pin "15") (pinfunction "VCC33_15") (pintype "bidirectional"))
      (node (ref "U3") (pin "19") (pinfunction "VCC33_19") (pintype "bidirectional"))
      (node (ref "U3") (pin "22") (pinfunction "VDDA_22") (pintype "bidirectional"))
      (node (ref "U3") (pin "30") (pinfunction "VCC33_30") (pintype "bidirectional"))
      (node (ref "U3") (pin "38") (pinfunction "VCCIO_38") (pintype "bidirectional"))
      (node (ref "U3") (pin "44") (pinfunction "VCCIO_44") (pintype "bidirectional"))
      (node (ref "U3") (pin "52") (pinfunction "VCCIO_52") (pintype "bidirectional"))
      (node (ref "U4") (pin "14") (pinfunction "VCCIO_3_14") (pintype "power_in"))
      (node (ref "U4") (pin "22") (pinfunction "VCCIO_3_22") (pintype "power_in"))
      (node (ref "U4") (pin "31") (pinfunction "VCCIO_2_31") (pintype "power_in"))
      (node (ref "U4") (pin "38") (pinfunction "VCCIO_2_38") (pintype "power_in"))
      (node (ref "U4") (pin "50") (pinfunction "VCC_SPI_50") (pintype "power_in"))
      (node (ref "U4") (pin "58") (pinfunction "VCCIO_1_58") (pintype "power_in"))
      (node (ref "U4") (pin "6") (pinfunction "VCCIO_3_6") (pintype "power_in"))
      (node (ref "U4") (pin "67") (pinfunction "VCCIO_1_67") (pintype "power_in"))
      (node (ref "U4") (pin "88") (pinfunction "VCCIO_0_88") (pintype "power_in"))
      (node (ref "U4") (pin "92") (pinfunction "VCCIO_0_92") (pintype "power_in"))
      (node (ref "U5") (pin "8") (pinfunction "VCC_8") (pintype "power_in"))
      (node (ref "Y1") (pin "1") (pinfunction "EN_1") (pintype "bidirectional"))
      (node (ref "Y1") (pin "4") (pinfunction "VCC_4") (pintype "bidirectional"))
    )
    (net (code "2") (name "BM_DM") (class "Default")
      (node (ref "IC3") (pin "32") (pinfunction "PA11_32") (pintype "bidirectional"))
      (node (ref "U2") (pin "42") (pinfunction "USB_DM_DN1_42") (pintype "bidirectional"))
    )
    (net (code "3") (name "BM_DP") (class "Default")
      (node (ref "IC3") (pin "33") (pinfunction "PA12_33") (pintype "bidirectional"))
      (node (ref "U2") (pin "41") (pinfunction "USB_DP_DN1_41") (pintype "bidirectional"))
    )
    (net (code "4") (name "BM_LED0") (class "Default")
      (node (ref "B1") (pin "A") (pinfunction "A_A") (pintype "passive"))
      (node (ref "IC3") (pin "20") (pinfunction "PB2_20") (pintype "bidirectional"))
    )
    (net (code "5") (name "BM_MISO") (class "Default")
      (node (ref "IC3") (pin "40") (pinfunction "PB4_40") (pintype "bidirectional"))
      (node (ref "U$1") (pin "A13") (pinfunction "A13_A13") (pintype "bidirectional"))
      (node (ref "U4") (pin "46") (pinfunction "IOB_45_SDI_46") (pintype "bidirectional"))
      (node (ref "U5") (pin "2") (pinfunction "MISO_2") (pintype "bidirectional"))
    )
    (net (code "6") (name "BM_MOSI") (class "Default")
      (node (ref "IC3") (pin "41") (pinfunction "PB5_41") (pintype "bidirectional"))
      (node (ref "U$1") (pin "A14") (pinfunction "A14_A14") (pintype "bidirectional"))
      (node (ref "U4") (pin "45") (pinfunction "IOB_44_SDO_45") (pintype "bidirectional"))
      (node (ref "U5") (pin "5") (pinfunction "MOSI_5") (pintype "bidirectional"))
    )
    (net (code "7") (name "BM_RST") (class "Default")
      (node (ref "IC3") (pin "7") (pinfunction "NRST_7") (pintype "bidirectional"))
      (node (ref "R7") (pin "1") (pinfunction "1_1") (pintype "passive"))
      (node (ref "U$1") (pin "B13") (pinfunction "B13_B13") (pintype "bidirectional"))
      (node (ref "U$2") (pin "10") (pinfunction "RESET_10") (pintype "bidirectional"))
    )
    (net (code "8") (name "BM_RX") (class "Default")
      (node (ref "IC3") (pin "13") (pinfunction "PA3_13") (pintype "bidirectional"))
      (node (ref "U$1") (pin "A17") (pinfunction "A17_A17") (pintype "bidirectional"))
      (node (ref "U4") (pin "57") (pinfunction "IOR_57_57") (pintype "bidirectional"))
    )
    (net (code "9") (name "BM_SCK") (class "Default")
      (node (ref "IC3") (pin "39") (pinfunction "PB3_39") (pintype "bidirectional"))
      (node (ref "U$1") (pin "A15") (pinfunction "A15_A15") (pintype "bidirectional"))
      (node (ref "U4") (pin "48") (pinfunction "IOB_46_SCK_48") (pintype "bidirectional"))
      (node (ref "U5") (pin "6") (pinfunction "SCK_6") (pintype "bidirectional"))
    )
    (net (code "10") (name "BM_TCK") (class "Default")
      (node (ref "IC3") (pin "37") (pinfunction "PA14_37") (pintype "bidirectional"))
      (node (ref "U$1") (pin "B16") (pinfunction "B16_B16") (pintype "bidirectional"))
      (node (ref "U$2") (pin "4") (pinfunction "TCK_4") (pintype "bidirectional"))
    )
    (net (code "11") (name "BM_TMS") (class "Default")
      (node (ref "IC3") (pin "34") (pinfunction "PA13_34") (pintype "bidirectional"))
      (node (ref "U$1") (pin "B17") (pinfunction "B17_B17") (pintype "bidirectional"))
      (node (ref "U$2") (pin "2") (pinfunction "TMS_2") (pintype "bidirectional"))
    )
    (net (code "12") (name "BM_TRGT_RST") (class "Default")
      (node (ref "IC3") (pin "18") (pinfunction "PB0_18") (pintype "bidirectional"))
      (node (ref "U4") (pin "54") (pinfunction "IOR_55_54") (pintype "bidirectional"))
    )
    (net (code "13") (name "BM_TRGT_SWDIO_IN") (class "Default")
      (node (ref "IC3") (pin "25") (pinfunction "PB12_25") (pintype "bidirectional"))
      (node (ref "R5") (pin "2") (pinfunction "2_2") (pintype "passive"))
    )
    (net (code "14") (name "BM_TRGT_TCK") (class "Default")
      (node (ref "IC3") (pin "26") (pinfunction "PB13_26") (pintype "bidirectional"))
      (node (ref "U4") (pin "51") (pinfunction "IOR_52_51") (pintype "bidirectional"))
    )
    (net (code "15") (name "BM_TRGT_TDI") (class "Default")
      (node (ref "IC3") (pin "17") (pinfunction "PA7_17") (pintype "bidirectional"))
      (node (ref "U4") (pin "56") (pinfunction "IOR_56_56") (pintype "bidirectional"))
    )
    (net (code "16") (name "BM_TRGT_TDO") (class "Default")
      (node (ref "IC3") (pin "31") (pinfunction "PA10_31") (pintype "bidirectional"))
      (node (ref "U4") (pin "53") (pinfunction "IOR_54_53") (pintype "bidirectional"))
    )
    (net (code "17") (name "BM_TRGT_TMS") (class "Default")
      (node (ref "IC3") (pin "27") (pinfunction "PB14_27") (pintype "bidirectional"))
      (node (ref "R5") (pin "1") (pinfunction "1_1") (pintype "passive"))
      (node (ref "U4") (pin "52") (pinfunction "IOR_53_52") (pintype "bidirectional"))
    )
    (net (code "18") (name "BM_TX") (class "Default")
      (node (ref "IC3") (pin "12") (pinfunction "PA2_12") (pintype "bidirectional"))
      (node (ref "U$1") (pin "A16") (pinfunction "A16_A16") (pintype "bidirectional"))
      (node (ref "U4") (pin "59") (pinfunction "IOR_58_59") (pintype "bidirectional"))
    )
    (net (code "19") (name "CC1") (class "Default")
      (node (ref "D3") (pin "1") (pinfunction "D1P_1") (pintype "bidirectional"))
      (node (ref "D3") (pin "14") (pinfunction "D1P_14") (pintype "bidirectional"))
      (node (ref "J2") (pin "A5") (pinfunction "CC1_A5") (pintype "passive"))
      (node (ref "U1") (pin "2") (pinfunction "CC1_2") (pintype "bidirectional"))
    )
    (net (code "20") (name "CC2") (class "Default")
      (node (ref "D3") (pin "13") (pinfunction "D1N_13") (pintype "bidirectional"))
      (node (ref "D3") (pin "2") (pinfunction "D1N_2") (pintype "bidirectional"))
      (node (ref "J2") (pin "B5") (pinfunction "CC2_B5") (pintype "passive"))
      (node (ref "U1") (pin "1") (pinfunction "CC2_1") (pintype "bidirectional"))
    )
    (net (code "21") (name "CH01") (class "Default")
      (node (ref "U$3") (pin "P$4") (pinfunction "4_P$4") (pintype "passive"))
      (node (ref "U4") (pin "60") (pinfunction "IOR_59_60") (pintype "bidirectional"))
    )
    (net (code "22") (name "CH02") (class "Default")
      (node (ref "U$3") (pin "P$6") (pinfunction "6_P$6") (pintype "passive"))
      (node (ref "U4") (pin "64") (pinfunction "IOR_63_64") (pintype "bidirectional"))
    )
    (net (code "23") (name "CH03") (class "Default")
      (node (ref "U$3") (pin "P$8") (pinfunction "8_P$8") (pintype "passive"))
      (node (ref "U4") (pin "66") (pinfunction "IOR_65_66") (pintype "bidirectional"))
    )
    (net (code "24") (name "CH04") (class "Default")
      (node (ref "U$3") (pin "P$10") (pinfunction "10_P$10") (pintype "passive"))
      (node (ref "U4") (pin "69") (pinfunction "IOR_68_69") (pintype "bidirectional"))
    )
    (net (code "25") (name "CH05") (class "Default")
      (node (ref "U$3") (pin "P$12") (pinfunction "12_P$12") (pintype "passive"))
      (node (ref "U4") (pin "72") (pinfunction "IOR_70_72") (pintype "bidirectional"))
    )
    (net (code "26") (name "CH06") (class "Default")
      (node (ref "U$3") (pin "P$14") (pinfunction "14_P$14") (pintype "passive"))
      (node (ref "U4") (pin "74") (pinfunction "IOR_72_74") (pintype "bidirectional"))
    )
    (net (code "27") (name "CH07") (class "Default")
      (node (ref "U$3") (pin "P$3") (pinfunction "3_P$3") (pintype "passive"))
      (node (ref "U4") (pin "63") (pinfunction "IOR_61_GBIN2_63") (pintype "bidirectional"))
    )
    (net (code "28") (name "CH08") (class "Default")
      (node (ref "U$3") (pin "P$5") (pinfunction "5_P$5") (pintype "passive"))
      (node (ref "U4") (pin "65") (pinfunction "IOR_64_65") (pintype "bidirectional"))
    )
    (net (code "29") (name "CH09") (class "Default")
      (node (ref "U$3") (pin "P$7") (pinfunction "7_P$7") (pintype "passive"))
      (node (ref "U4") (pin "68") (pinfunction "IOR_67_68") (pintype "bidirectional"))
    )
    (net (code "30") (name "CH10") (class "Default")
      (node (ref "U$3") (pin "P$9") (pinfunction "9_P$9") (pintype "passive"))
      (node (ref "U4") (pin "71") (pinfunction "IOR_69_71") (pintype "bidirectional"))
    )
    (net (code "31") (name "CH11") (class "Default")
      (node (ref "U$3") (pin "P$11") (pinfunction "11_P$11") (pintype "passive"))
      (node (ref "U4") (pin "73") (pinfunction "IOR_71_73") (pintype "bidirectional"))
    )
    (net (code "32") (name "CH12") (class "Default")
      (node (ref "U$3") (pin "P$13") (pinfunction "13_P$13") (pintype "passive"))
      (node (ref "U4") (pin "78") (pinfunction "IOT_73_78") (pintype "bidirectional"))
    )
    (net (code "33") (name "CH13") (class "Default")
      (node (ref "U$4") (pin "P$4") (pinfunction "4_P$4") (pintype "passive"))
      (node (ref "U4") (pin "79") (pinfunction "IOT_74_79") (pintype "bidirectional"))
    )
    (net (code "34") (name "CH14") (class "Default")
      (node (ref "U$4") (pin "P$6") (pinfunction "6_P$6") (pintype "passive"))
      (node (ref "U4") (pin "81") (pinfunction "IOT_77_81") (pintype "bidirectional"))
    )
    (net (code "35") (name "CH15") (class "Default")
      (node (ref "U$4") (pin "P$8") (pinfunction "8_P$8") (pintype "passive"))
      (node (ref "U4") (pin "85") (pinfunction "IOT_80_85") (pintype "bidirectional"))
    )
    (net (code "36") (name "CH16") (class "Default")
      (node (ref "U$4") (pin "P$10") (pinfunction "10_P$10") (pintype "passive"))
      (node (ref "U4") (pin "87") (pinfunction "IOT_82_87") (pintype "bidirectional"))
    )
    (net (code "37") (name "CH17") (class "Default")
      (node (ref "U$4") (pin "P$12") (pinfunction "12_P$12") (pintype "passive"))
      (node (ref "U4") (pin "90") (pinfunction "IOT_85_GBIN0_90") (pintype "bidirectional"))
    )
    (net (code "38") (name "CH18") (class "Default")
      (node (ref "U$4") (pin "P$14") (pinfunction "14_P$14") (pintype "passive"))
      (node (ref "U4") (pin "93") (pinfunction "IOT_87_93") (pintype "bidirectional"))
    )
    (net (code "39") (name "CH19") (class "Default")
      (node (ref "U$4") (pin "P$16") (pinfunction "16_P$16") (pintype "passive"))
      (node (ref "U4") (pin "95") (pinfunction "IOT_89_95") (pintype "bidirectional"))
    )
    (net (code "40") (name "CH20") (class "Default")
      (node (ref "U$4") (pin "P$18") (pinfunction "18_P$18") (pintype "passive"))
      (node (ref "U4") (pin "97") (pinfunction "IOT_91_97") (pintype "bidirectional"))
    )
    (net (code "41") (name "CH21") (class "Default")
      (node (ref "U$4") (pin "P$20") (pinfunction "20_P$20") (pintype "passive"))
      (node (ref "U4") (pin "100") (pinfunction "IOT_95_100") (pintype "bidirectional"))
    )
    (net (code "42") (name "CH22") (class "Default")
      (node (ref "U$4") (pin "P$22") (pinfunction "22_P$22") (pintype "passive"))
      (node (ref "U4") (pin "41") (pinfunction "IOB_42_CBSEL0_41") (pintype "bidirectional"))
    )
    (net (code "43") (name "CH23") (class "Default")
      (node (ref "U$4") (pin "P$3") (pinfunction "3_P$3") (pintype "passive"))
      (node (ref "U4") (pin "80") (pinfunction "IOT_75_80") (pintype "bidirectional"))
    )
    (net (code "44") (name "CH24") (class "Default")
      (node (ref "U$4") (pin "P$5") (pinfunction "5_P$5") (pintype "passive"))
      (node (ref "U4") (pin "82") (pinfunction "IOT_78_82") (pintype "bidirectional"))
    )
    (net (code "45") (name "CH25") (class "Default")
      (node (ref "R11") (pin "16") (pinfunction "16_16") (pintype "passive"))
      (node (ref "U$4") (pin "P$7") (pinfunction "7_P$7") (pintype "passive"))
      (node (ref "U4") (pin "83") (pinfunction "IOT_79_83") (pintype "bidirectional"))
    )
    (net (code "46") (name "CH26") (class "Default")
      (node (ref "R11") (pin "15") (pinfunction "15_15") (pintype "passive"))
      (node (ref "U$4") (pin "P$9") (pinfunction "9_P$9") (pintype "passive"))
      (node (ref "U4") (pin "86") (pinfunction "IOT_81_86") (pintype "bidirectional"))
    )
    (net (code "47") (name "CH27") (class "Default")
      (node (ref "R11") (pin "14") (pinfunction "14_14") (pintype "passive"))
      (node (ref "U$4") (pin "P$11") (pinfunction "11_P$11") (pintype "passive"))
      (node (ref "U4") (pin "89") (pinfunction "IOT_84_GBIN1_89") (pintype "bidirectional"))
    )
    (net (code "48") (name "CH28") (class "Default")
      (node (ref "R11") (pin "13") (pinfunction "13_13") (pintype "passive"))
      (node (ref "U$4") (pin "P$13") (pinfunction "13_P$13") (pintype "passive"))
      (node (ref "U4") (pin "91") (pinfunction "IOT_86_91") (pintype "bidirectional"))
    )
    (net (code "49") (name "CH29") (class "Default")
      (node (ref "R11") (pin "12") (pinfunction "12_12") (pintype "passive"))
      (node (ref "U$4") (pin "P$15") (pinfunction "15_P$15") (pintype "passive"))
      (node (ref "U4") (pin "94") (pinfunction "IOT_88_94") (pintype "bidirectional"))
    )
    (net (code "50") (name "CH30") (class "Default")
      (node (ref "R11") (pin "11") (pinfunction "11_11") (pintype "passive"))
      (node (ref "U$4") (pin "P$17") (pinfunction "17_P$17") (pintype "passive"))
      (node (ref "U4") (pin "96") (pinfunction "IOT_90_96") (pintype "bidirectional"))
    )
    (net (code "51") (name "CH31") (class "Default")
      (node (ref "R11") (pin "10") (pinfunction "10_10") (pintype "passive"))
      (node (ref "U$4") (pin "P$19") (pinfunction "19_P$19") (pintype "passive"))
      (node (ref "U4") (pin "99") (pinfunction "IOT_93_99") (pintype "bidirectional"))
    )
    (net (code "52") (name "CH32") (class "Default")
      (node (ref "R11") (pin "9") (pinfunction "9_9") (pintype "passive"))
      (node (ref "U$4") (pin "P$21") (pinfunction "21_P$21") (pintype "passive"))
      (node (ref "U4") (pin "1") (pinfunction "IOL_1A_1") (pintype "bidirectional"))
    )
    (net (code "53") (name "DN_UP") (class "Default")
      (node (ref "D3") (pin "12") (pinfunction "D2P_12") (pintype "bidirectional"))
      (node (ref "D3") (pin "3") (pinfunction "D2P_3") (pintype "bidirectional"))
      (node (ref "J2") (pin "A7") (pinfunction "DN1_A7") (pintype "passive"))
      (node (ref "J2") (pin "B7") (pinfunction "DN2_B7") (pintype "passive"))
      (node (ref "U2") (pin "27") (pinfunction "USB_DM_UP_27") (pintype "bidirectional"))
    )
    (net (code "54") (name "DP_UP") (class "Default")
      (node (ref "D3") (pin "11") (pinfunction "D2N_11") (pintype "bidirectional"))
      (node (ref "D3") (pin "4") (pinfunction "D2N_4") (pintype "bidirectional"))
      (node (ref "J2") (pin "A6") (pinfunction "DP1_A6") (pintype "passive"))
      (node (ref "J2") (pin "B6") (pinfunction "DP2_B6") (pintype "passive"))
      (node (ref "U2") (pin "26") (pinfunction "USB_DP_UP_26") (pintype "bidirectional"))
    )
    (net (code "55") (name "FT_BE0") (class "Default")
      (node (ref "U3") (pin "2") (pinfunction "BE_0_2") (pintype "bidirectional"))
      (node (ref "U4") (pin "40") (pinfunction "IOB_41_40") (pintype "bidirectional"))
    )
    (net (code "56") (name "FT_BE1") (class "Default")
      (node (ref "U3") (pin "3") (pinfunction "BE_1_3") (pintype "bidirectional"))
      (node (ref "U4") (pin "37") (pinfunction "IOB_37_37") (pintype "bidirectional"))
    )
    (net (code "57") (name "FT_CLK") (class "Default")
      (node (ref "U3") (pin "43") (pinfunction "CLK_43") (pintype "bidirectional"))
      (node (ref "U4") (pin "13") (pinfunction "IOL_6B_GBIN7_13") (pintype "bidirectional"))
    )
    (net (code "58") (name "FT_D0") (class "Default")
      (node (ref "U3") (pin "33") (pinfunction "D0_33") (pintype "bidirectional"))
      (node (ref "U4") (pin "25") (pinfunction "IOL_12B_25") (pintype "bidirectional"))
    )
    (net (code "59") (name "FT_D1") (class "Default")
      (node (ref "U3") (pin "34") (pinfunction "D1_34") (pintype "bidirectional"))
      (node (ref "U4") (pin "24") (pinfunction "IOL_12A_24") (pintype "bidirectional"))
    )
    (net (code "60") (name "FT_D2") (class "Default")
      (node (ref "U3") (pin "35") (pinfunction "D2_35") (pintype "bidirectional"))
      (node (ref "U4") (pin "21") (pinfunction "IOL_10B_21") (pintype "bidirectional"))
    )
    (net (code "61") (name "FT_D3") (class "Default")
      (node (ref "U3") (pin "36") (pinfunction "D3_36") (pintype "bidirectional"))
      (node (ref "U4") (pin "20") (pinfunction "IOL_10A_20") (pintype "bidirectional"))
    )
    (net (code "62") (name "FT_D4") (class "Default")
      (node (ref "U3") (pin "39") (pinfunction "D4_39") (pintype "bidirectional"))
      (node (ref "U4") (pin "19") (pinfunction "IOL_8B_19") (pintype "bidirectional"))
    )
    (net (code "63") (name "FT_D5") (class "Default")
      (node (ref "U3") (pin "40") (pinfunction "D5_40") (pintype "bidirectional"))
      (node (ref "U4") (pin "18") (pinfunction "IOL_8A_18") (pintype "bidirectional"))
    )
    (net (code "64") (name "FT_D6") (class "Default")
      (node (ref "U3") (pin "41") (pinfunction "D6_41") (pintype "bidirectional"))
      (node (ref "U4") (pin "16") (pinfunction "IOL_7B_16") (pintype "bidirectional"))
    )
    (net (code "65") (name "FT_D7") (class "Default")
      (node (ref "U3") (pin "42") (pinfunction "D7_42") (pintype "bidirectional"))
      (node (ref "U4") (pin "15") (pinfunction "IOL_7A_GBIN6_15") (pintype "bidirectional"))
    )
    (net (code "66") (name "FT_D8") (class "Default")
      (node (ref "U3") (pin "45") (pinfunction "D8_45") (pintype "bidirectional"))
      (node (ref "U4") (pin "12") (pinfunction "IOL_6A_12") (pintype "bidirectional"))
    )
    (net (code "67") (name "FT_D9") (class "Default")
      (node (ref "U3") (pin "46") (pinfunction "D9_46") (pintype "bidirectional"))
      (node (ref "U4") (pin "10") (pinfunction "IOL_5B_10") (pintype "bidirectional"))
    )
    (net (code "68") (name "FT_D10") (class "Default")
      (node (ref "U3") (pin "47") (pinfunction "D10_47") (pintype "bidirectional"))
      (node (ref "U4") (pin "9") (pinfunction "IOL_5A_9") (pintype "bidirectional"))
    )
    (net (code "69") (name "FT_D11") (class "Default")
      (node (ref "U3") (pin "48") (pinfunction "D11_48") (pintype "bidirectional"))
      (node (ref "U4") (pin "8") (pinfunction "IOL_3B_8") (pintype "bidirectional"))
    )
    (net (code "70") (name "FT_D12") (class "Default")
      (node (ref "U3") (pin "53") (pinfunction "D12_53") (pintype "bidirectional"))
      (node (ref "U4") (pin "7") (pinfunction "IOL_3A_7") (pintype "bidirectional"))
    )
    (net (code "71") (name "FT_D13") (class "Default")
      (node (ref "U3") (pin "54") (pinfunction "D13_54") (pintype "bidirectional"))
      (node (ref "U4") (pin "4") (pinfunction "IOL_2B_4") (pintype "bidirectional"))
    )
    (net (code "72") (name "FT_D14") (class "Default")
      (node (ref "U3") (pin "55") (pinfunction "D14_55") (pintype "bidirectional"))
      (node (ref "U4") (pin "3") (pinfunction "IOL_2A_3") (pintype "bidirectional"))
    )
    (net (code "73") (name "FT_D15") (class "Default")
      (node (ref "U3") (pin "56") (pinfunction "D15_56") (pintype "bidirectional"))
      (node (ref "U4") (pin "2") (pinfunction "IOL_1B_2") (pintype "bidirectional"))
    )
    (net (code "74") (name "FT_DM") (class "Default")
      (node (ref "U2") (pin "15") (pinfunction "USB_DM_DN2_15") (pintype "bidirectional"))
      (node (ref "U3") (pin "20") (pinfunction "D-_20") (pintype "bidirectional"))
    )
    (net (code "75") (name "FT_DP") (class "Default")
      (node (ref "U2") (pin "14") (pinfunction "USB_DP_DN2_14") (pintype "bidirectional"))
      (node (ref "U3") (pin "18") (pinfunction "D+_18") (pintype "bidirectional"))
    )
    (net (code "76") (name "FT_DV10") (class "Default")
      (node (ref "C13") (pin "1") (pinfunction "1_1") (pintype "passive"))
      (node (ref "U3") (pin "1") (pinfunction "AVDD_1") (pintype "bidirectional"))
      (node (ref "U3") (pin "23") (pinfunction "VD10_23") (pintype "bidirectional"))
      (node (ref "U3") (pin "26") (pinfunction "VD10_26") (pintype "bidirectional"))
      (node (ref "U3") (pin "31") (pinfunction "DV10_31") (pintype "bidirectional"))
      (node (ref "U3") (pin "37") (pinfunction "VD10_37") (pintype "bidirectional"))
      (node (ref "U3") (pin "50") (pinfunction "VD10_50") (pintype "bidirectional"))
    )
    (net (code "77") (name "FT_GPIO_0") (class "Default")
      (node (ref "U3") (pin "12") (pinfunction "GPIO0_12") (pintype "bidirectional"))
      (node (ref "U4") (pin "27") (pinfunction "IOB_27_27") (pintype "bidirectional"))
    )
    (net (code "78") (name "FT_GPIO_1") (class "Default")
      (node (ref "U3") (pin "13") (pinfunction "GPIO1_13") (pintype "bidirectional"))
      (node (ref "U4") (pin "26") (pinfunction "IOB_26_26") (pintype "bidirectional"))
    )
    (net (code "79") (name "FT_OE") (class "Default")
      (node (ref "U3") (pin "9") (pinfunction "~{OE}_9") (pintype "bidirectional"))
      (node (ref "U4") (pin "28") (pinfunction "IOB_28_28") (pintype "bidirectional"))
    )
    (net (code "80") (name "FT_RD") (class "Default")
      (node (ref "U3") (pin "8") (pinfunction "~{RD}_8") (pintype "bidirectional"))
      (node (ref "U4") (pin "29") (pinfunction "IOB_29_29") (pintype "bidirectional"))
    )
    (net (code "81") (name "FT_RST") (class "Default")
      (node (ref "R26") (pin "1") (pinfunction "1_1") (pintype "passive"))
      (node (ref "U3") (pin "10") (pinfunction "~{RESET}_10") (pintype "bidirectional"))
    )
    (net (code "82") (name "FT_RXF") (class "Default")
      (node (ref "U3") (pin "5") (pinfunction "~{RXF}_5") (pintype "bidirectional"))
      (node (ref "U4") (pin "34") (pinfunction "IOB_36_GBIN4_34") (pintype "bidirectional"))
    )
    (net (code "83") (name "FT_SIWU") (class "Default")
      (node (ref "R25") (pin "1") (pinfunction "1_1") (pintype "passive"))
      (node (ref "U3") (pin "6") (pinfunction "~{SIWU}_6") (pintype "bidirectional"))
    )
    (net (code "84") (name "FT_SSRXM") (class "Default")
      (node (ref "U2") (pin "17") (pinfunction "USB_SSTXM_DN2_17") (pintype "bidirectional"))
      (node (ref "U3") (pin "27") (pinfunction "RID-_27") (pintype "bidirectional"))
    )
    (net (code "85") (name "FT_SSRXP") (class "Default")
      (node (ref "U2") (pin "16") (pinfunction "USB_SSTXP_DN2_16") (pintype "bidirectional"))
      (node (ref "U3") (pin "28") (pinfunction "RID+_28") (pintype "bidirectional"))
    )
    (net (code "86") (name "FT_SSTXM") (class "Default")
      (node (ref "C17") (pin "2") (pinfunction "2_2") (pintype "passive"))
      (node (ref "U2") (pin "20") (pinfunction "USB_SSRXM_DN2_20") (pintype "bidirectional"))
    )
    (net (code "87") (name "FT_SSTXM_C") (class "Default")
      (node (ref "C17") (pin "1") (pinfunction "1_1") (pintype "passive"))
      (node (ref "U3") (pin "24") (pinfunction "TOD-_24") (pintype "bidirectional"))
    )
    (net (code "88") (name "FT_SSTXP") (class "Default")
      (node (ref "C16") (pin "2") (pinfunction "2_2") (pintype "passive"))
      (node (ref "U2") (pin "19") (pinfunction "USB_SSRXP_DN2_19") (pintype "bidirectional"))
    )
    (net (code "89") (name "FT_SSTXP_C") (class "Default")
      (node (ref "C16") (pin "1") (pinfunction "1_1") (pintype "passive"))
      (node (ref "U3") (pin "25") (pinfunction "TOD+_25") (pintype "bidirectional"))
    )
    (net (code "90") (name "FT_TXE") (class "Default")
      (node (ref "U3") (pin "4") (pinfunction "~{TXE}_4") (pintype "bidirectional"))
      (node (ref "U4") (pin "36") (pinfunction "IOB_34_36") (pintype "bidirectional"))
    )
    (net (code "91") (name "FT_VUSB_DET") (class "Default")
      (node (ref "R10") (pin "2") (pinfunction "2_2") (pintype "passive"))
      (node (ref "R9") (pin "1") (pinfunction "1_1") (pintype "passive"))
      (node (ref "U3") (pin "29") (pinfunction "VBUS_29") (pintype "bidirectional"))
    )
    (net (code "92") (name "FT_WR") (class "Default")
      (node (ref "U3") (pin "7") (pinfunction "~{WR}_7") (pintype "bidirectional"))
      (node (ref "U4") (pin "30") (pinfunction "IOB_30_30") (pintype "bidirectional"))
    )
    (net (code "93") (name "GND") (class "Default")
      (node (ref "B10") (pin "C") (pinfunction "C_C") (pintype "passive"))
      (node (ref "B11") (pin "C") (pinfunction "C_C") (pintype "passive"))
      (node (ref "B12") (pin "C") (pinfunction "C_C") (pintype "passive"))
      (node (ref "B13") (pin "C") (pinfunction "C_C") (pintype "passive"))
      (node (ref "B14") (pin "C") (pinfunction "C_C") (pintype "passive"))
      (node (ref "B15") (pin "C") (pinfunction "C_C") (pintype "passive"))
      (node (ref "B8") (pin "C") (pinfunction "C_C") (pintype "passive"))
      (node (ref "B9") (pin "C") (pinfunction "C_C") (pintype "passive"))
      (node (ref "C1") (pin "2") (pinfunction "2_2") (pintype "passive"))
      (node (ref "C10") (pin "2") (pinfunction "2_2") (pintype "passive"))
      (node (ref "C11") (pin "2") (pinfunction "2_2") (pintype "passive"))
      (node (ref "C12") (pin "2") (pinfunction "2_2") (pintype "passive"))
      (node (ref "C13") (pin "2") (pinfunction "2_2") (pintype "passive"))
      (node (ref "C14") (pin "2") (pinfunction "2_2") (pintype "passive"))
      (node (ref "C15") (pin "2") (pinfunction "2_2") (pintype "passive"))
      (node (ref "C2") (pin "2") (pinfunction "2_2") (pintype "passive"))
      (node (ref "C20") (pin "2") (pinfunction "2_2") (pintype "passive"))
      (node (ref "C21") (pin "2") (pinfunction "2_2") (pintype "passive"))
      (node (ref "C22") (pin "2") (pinfunction "2_2") (pintype "passive"))
      (node (ref "C26") (pin "2") (pinfunction "2_2") (pintype "passive"))
      (node (ref "C27") (pin "2") (pinfunction "2_2") (pintype "passive"))
      (node (ref "C28") (pin "2") (pinfunction "2_2") (pintype "passive"))
      (node (ref "C3") (pin "2") (pinfunction "2_2") (pintype "passive"))
      (node (ref "C30") (pin "2") (pinfunction "2_2") (pintype "passive"))
      (node (ref "C35") (pin "2") (pinfunction "2_2") (pintype "passive"))
      (node (ref "C36") (pin "2") (pinfunction "2_2") (pintype "passive"))
      (node (ref "C37") (pin "2") (pinfunction "2_2") (pintype "passive"))
      (node (ref "C38") (pin "2") (pinfunction "2_2") (pintype "passive"))
      (node (ref "C4") (pin "2") (pinfunction "2_2") (pintype "passive"))
      (node (ref "C5") (pin "2") (pinfunction "2_2") (pintype "passive"))
      (node (ref "C6") (pin "2") (pinfunction "2_2") (pintype "passive"))
      (node (ref "C600") (pin "2") (pinfunction "2_2") (pintype "passive"))
      (node (ref "C601") (pin "2") (pinfunction "2_2") (pintype "passive"))
      (node (ref "C602") (pin "2") (pinfunction "2_2") (pintype "passive"))
      (node (ref "C603") (pin "2") (pinfunction "2_2") (pintype "passive"))
      (node (ref "C610") (pin "2") (pinfunction "2_2") (pintype "passive"))
      (node (ref "C611") (pin "2") (pinfunction "2_2") (pintype "passive"))
      (node (ref "C612") (pin "2") (pinfunction "2_2") (pintype "passive"))
      (node (ref "C613") (pin "2") (pinfunction "2_2") (pintype "passive"))
      (node (ref "C620") (pin "2") (pinfunction "2_2") (pintype "passive"))
      (node (ref "C621") (pin "2") (pinfunction "2_2") (pintype "passive"))
      (node (ref "C622") (pin "2") (pinfunction "2_2") (pintype "passive"))
      (node (ref "C623") (pin "2") (pinfunction "2_2") (pintype "passive"))
      (node (ref "C630") (pin "2") (pinfunction "2_2") (pintype "passive"))
      (node (ref "C631") (pin "2") (pinfunction "2_2") (pintype "passive"))
      (node (ref "C632") (pin "2") (pinfunction "2_2") (pintype "passive"))
      (node (ref "C633") (pin "2") (pinfunction "2_2") (pintype "passive"))
      (node (ref "C650") (pin "2") (pinfunction "2_2") (pintype "passive"))
      (node (ref "C651") (pin "2") (pinfunction "2_2") (pintype "passive"))
      (node (ref "C652") (pin "2") (pinfunction "2_2") (pintype "passive"))
      (node (ref "C653") (pin "2") (pinfunction "2_2") (pintype "passive"))
      (node (ref "C654") (pin "2") (pinfunction "2_2") (pintype "passive"))
      (node (ref "C655") (pin "2") (pinfunction "2_2") (pintype "passive"))
      (node (ref "C656") (pin "2") (pinfunction "2_2") (pintype "passive"))
      (node (ref "C7") (pin "2") (pinfunction "2_2") (pintype "passive"))
      (node (ref "C8") (pin "2") (pinfunction "2_2") (pintype "passive"))
      (node (ref "C9") (pin "2") (pinfunction "2_2") (pintype "passive"))
      (node (ref "D1") (pin "3") (pinfunction "GND_3") (pintype "power_in"))
      (node (ref "D1") (pin "8") (pinfunction "GND_8") (pintype "power_in"))
      (node (ref "D2") (pin "3") (pinfunction "GND_3") (pintype "power_in"))
      (node (ref "D2") (pin "8") (pinfunction "GND_8") (pintype "power_in"))
      (node (ref "D3") (pin "10") (pinfunction "GND_10") (pintype "power_in"))
      (node (ref "D3") (pin "5") (pinfunction "GND_5") (pintype "power_in"))
      (node (ref "D6") (pin "A") (pinfunction "A_A") (pintype "passive"))
      (node (ref "D7") (pin "A") (pinfunction "A_A") (pintype "passive"))
      (node (ref "IC3") (pin "23") (pinfunction "VSS_23") (pintype "power_in"))
      (node (ref "IC3") (pin "35") (pinfunction "VSS_35") (pintype "power_in"))
      (node (ref "IC3") (pin "47") (pinfunction "VSS_47") (pintype "power_in"))
      (node (ref "IC3") (pin "8") (pinfunction "VSSA_8") (pintype "power_in"))
      (node (ref "J2") (pin "A1") (pinfunction "GND_A1") (pintype "passive"))
      (node (ref "J2") (pin "A12") (pinfunction "GND_A12") (pintype "passive"))
      (node (ref "J2") (pin "B1") (pinfunction "GND_B1") (pintype "passive"))
      (node (ref "J2") (pin "B12") (pinfunction "GND_B12") (pintype "passive"))
      (node (ref "J2") (pin "SH1") (pinfunction "SHIELD_SH1") (pintype "passive"))
      (node (ref "J2") (pin "SH2") (pinfunction "SHIELD_SH2") (pintype "passive"))
      (node (ref "J2") (pin "SH3") (pinfunction "SHIELD_SH3") (pintype "passive"))
      (node (ref "J2") (pin "SH4") (pinfunction "SHIELD_SH4") (pintype "passive"))
      (node (ref "R1") (pin "1") (pinfunction "1_1") (pintype "passive"))
      (node (ref "R10") (pin "1") (pinfunction "1_1") (pintype "passive"))
      (node (ref "R13") (pin "1") (pinfunction "1_1") (pintype "passive"))
      (node (ref "R17") (pin "2") (pinfunction "2_2") (pintype "passive"))
      (node (ref "R18") (pin "1") (pinfunction "1_1") (pintype "passive"))
      (node (ref "R19") (pin "1") (pinfunction "1_1") (pintype "passive"))
      (node (ref "R20") (pin "1") (pinfunction "1_1") (pintype "passive"))
      (node (ref "R22") (pin "1") (pinfunction "1_1") (pintype "passive"))
      (node (ref "R23") (pin "1") (pinfunction "1_1") (pintype "passive"))
      (node (ref "R3") (pin "1") (pinfunction "1_1") (pintype "passive"))
      (node (ref "R6") (pin "1") (pinfunction "1_1") (pintype "passive"))
      (node (ref "R8") (pin "1") (pinfunction "1_1") (pintype "passive"))
      (node (ref "S2") (pin "1") (pinfunction "1_1") (pintype "passive"))
      (node (ref "U$1") (pin "A11") (pinfunction "A11_A11") (pintype "bidirectional"))
      (node (ref "U$1") (pin "A12") (pinfunction "A12_A12") (pintype "bidirectional"))
      (node (ref "U$1") (pin "B11") (pinfunction "B11_B11") (pintype "bidirectional"))
      (node (ref "U$1") (pin "B12") (pinfunction "B12_B12") (pintype "bidirectional"))
      (node (ref "U$2") (pin "3") (pinfunction "GND_3") (pintype "bidirectional"))
      (node (ref "U$2") (pin "5") (pinfunction "NC_5") (pintype "bidirectional"))
      (node (ref "U$2") (pin "9") (pinfunction "~{TRST}_9") (pintype "bidirectional"))
      (node (ref "U$3") (pin "P$1") (pinfunction "1_P$1") (pintype "passive"))
      (node (ref "U$3") (pin "P$2") (pinfunction "2_P$2") (pintype "passive"))
      (node (ref "U$4") (pin "P$1") (pinfunction "1_P$1") (pintype "passive"))
      (node (ref "U$4") (pin "P$2") (pinfunction "2_P$2") (pintype "passive"))
      (node (ref "U1") (pin "12") (pinfunction "~{ENN_MUX}_12") (pintype "input"))
      (node (ref "U1") (pin "13") (pinfunction "GND_13") (pintype "power_in"))
      (node (ref "U1") (pin "28") (pinfunction "GND_28") (pintype "power_in"))
      (node (ref "U1") (pin "31") (pinfunction "EXP_PAD_31") (pintype "power_in"))
      (node (ref "U2") (pin "P$1") (pinfunction "PAD_P$1") (pintype "bidirectional"))
      (node (ref "U3") (pin "32") (pinfunction "GND_32") (pintype "bidirectional"))
      (node (ref "U3") (pin "49") (pinfunction "GND_49") (pintype "bidirectional"))
      (node (ref "U3") (pin "51") (pinfunction "GND_51") (pintype "bidirectional"))
      (node (ref "U3") (pin "PAD") (pinfunction "GND_PAD") (pintype "bidirectional"))
      (node (ref "U4") (pin "17") (pinfunction "GND_17") (pintype "power_in"))
      (node (ref "U4") (pin "23") (pinfunction "GND_23") (pintype "power_in"))
      (node (ref "U4") (pin "32") (pinfunction "GND_32") (pintype "power_in"))
      (node (ref "U4") (pin "39") (pinfunction "GND_39") (pintype "power_in"))
      (node (ref "U4") (pin "47") (pinfunction "GND_47") (pintype "power_in"))
      (node (ref "U4") (pin "5") (pinfunction "GND_5") (pintype "power_in"))
      (node (ref "U4") (pin "55") (pinfunction "GND_55") (pintype "power_in"))
      (node (ref "U4") (pin "70") (pinfunction "GND_70") (pintype "power_in"))
      (node (ref "U4") (pin "84") (pinfunction "GND_84") (pintype "power_in"))
      (node (ref "U4") (pin "98") (pinfunction "GND_98") (pintype "power_in"))
      (node (ref "U5") (pin "4") (pinfunction "GND_4") (pintype "power_in"))
      (node (ref "U7") (pin "10") (pinfunction "SEQ_10") (pintype "bidirectional"))
      (node (ref "U7") (pin "4") (pinfunction "GND_4") (pintype "bidirectional"))
      (node (ref "U7") (pin "5") (pinfunction "~{EN1}_5") (pintype "bidirectional"))
      (node (ref "U7") (pin "6") (pinfunction "~{EN2}_6") (pintype "bidirectional"))
      (node (ref "U7") (pin "9") (pinfunction "ILIM2_9") (pintype "bidirectional"))
      (node (ref "U7") (pin "EXP") (pinfunction "GND_EXP") (pintype "bidirectional"))
      (node (ref "Y1") (pin "2") (pinfunction "GND_2") (pintype "bidirectional"))
    )
    (net (code "94") (name "ICE_CDONE") (class "Default")
      (node (ref "IC3") (pin "42") (pinfunction "PB6_42") (pintype "bidirectional"))
      (node (ref "U$1") (pin "B8") (pinfunction "B8_B8") (pintype "bidirectional"))
      (node (ref "U4") (pin "43") (pinfunction "CDONE_43") (pintype "input"))
    )
    (net (code "95") (name "ICE_CLK") (class "Default")
      (node (ref "U4") (pin "33") (pinfunction "IOB_35_GBIN5_33") (pintype "bidirectional"))
      (node (ref "Y1") (pin "3") (pinfunction "OUT_3") (pintype "bidirectional"))
    )
    (net (code "96") (name "ICE_CRESET") (class "Default")
      (node (ref "IC3") (pin "43") (pinfunction "PB7_43") (pintype "bidirectional"))
      (node (ref "U$1") (pin "B9") (pinfunction "B9_B9") (pintype "bidirectional"))
      (node (ref "U4") (pin "44") (pinfunction "CRESET_B_44") (pintype "input"))
    )
    (net (code "97") (name "ICE_RESET") (class "Default")
      (node (ref "R24") (pin "1") (pinfunction "1_1") (pintype "passive"))
      (node (ref "S2") (pin "3") (pinfunction "3_3") (pintype "passive"))
      (node (ref "U4") (pin "62") (pinfunction "IOR_60_GBIN3_62") (pintype "bidirectional"))
    )
    (net (code "98") (name "ICE_SS") (class "Default")
      (node (ref "IC3") (pin "45") (pinfunction "PB8_45") (pintype "bidirectional"))
      (node (ref "U$1") (pin "B10") (pinfunction "B10_B10") (pintype "bidirectional"))
      (node (ref "U4") (pin "49") (pinfunction "IOB_47_SS_49") (pintype "bidirectional"))
      (node (ref "U5") (pin "1") (pinfunction "CS_1") (pintype "bidirectional"))
    )
    (net (code "99") (name "Net-(B1-PadC)") (class "Default")
      (node (ref "B1") (pin "C") (pinfunction "C_C") (pintype "passive"))
      (node (ref "R19") (pin "2") (pinfunction "2_2") (pintype "passive"))
    )
    (net (code "100") (name "Net-(B2-PadC)") (class "Default")
      (node (ref "B2") (pin "C") (pinfunction "C_C") (pintype "passive"))
      (node (ref "R20") (pin "2") (pinfunction "2_2") (pintype "passive"))
    )
    (net (code "101") (name "Net-(B8-PadA)") (class "Default")
      (node (ref "B8") (pin "A") (pinfunction "A_A") (pintype "passive"))
      (node (ref "R11") (pin "1") (pinfunction "1_1") (pintype "passive"))
    )
    (net (code "102") (name "Net-(B9-PadA)") (class "Default")
      (node (ref "B9") (pin "A") (pinfunction "A_A") (pintype "passive"))
      (node (ref "R11") (pin "2") (pinfunction "2_2") (pintype "passive"))
    )
    (net (code "103") (name "Net-(B10-PadA)") (class "Default")
      (node (ref "B10") (pin "A") (pinfunction "A_A") (pintype "passive"))
      (node (ref "R11") (pin "3") (pinfunction "3_3") (pintype "passive"))
    )
    (net (code "104") (name "Net-(B11-PadA)") (class "Default")
      (node (ref "B11") (pin "A") (pinfunction "A_A") (pintype "passive"))
      (node (ref "R11") (pin "4") (pinfunction "4_4") (pintype "passive"))
    )
    (net (code "105") (name "Net-(B12-PadA)") (class "Default")
      (node (ref "B12") (pin "A") (pinfunction "A_A") (pintype "passive"))
      (node (ref "R11") (pin "5") (pinfunction "5_5") (pintype "passive"))
    )
    (net (code "106") (name "Net-(B13-PadA)") (class "Default")
      (node (ref "B13") (pin "A") (pinfunction "A_A") (pintype "passive"))
      (node (ref "R11") (pin "6") (pinfunction "6_6") (pintype "passive"))
    )
    (net (code "107") (name "Net-(B14-PadA)") (class "Default")
      (node (ref "B14") (pin "A") (pinfunction "A_A") (pintype "passive"))
      (node (ref "R11") (pin "7") (pinfunction "7_7") (pintype "passive"))
    )
    (net (code "108") (name "Net-(B15-PadA)") (class "Default")
      (node (ref "B15") (pin "A") (pinfunction "A_A") (pintype "passive"))
      (node (ref "R11") (pin "8") (pinfunction "8_8") (pintype "passive"))
    )
    (net (code "109") (name "Net-(C19-Pad2)") (class "Default")
      (node (ref "C19") (pin "2") (pinfunction "2_2") (pintype "passive"))
      (node (ref "R1") (pin "2") (pinfunction "2_2") (pintype "passive"))
    )
    (net (code "110") (name "Net-(C25-Pad2)") (class "Default")
      (node (ref "C25") (pin "2") (pinfunction "2_2") (pintype "passive"))
      (node (ref "R3") (pin "2") (pinfunction "2_2") (pintype "passive"))
    )
    (net (code "111") (name "Net-(IC3A-BOOT0)") (class "Default")
      (node (ref "IC3") (pin "44") (pinfunction "BOOT0_44") (pintype "input"))
      (node (ref "R8") (pin "2") (pinfunction "2_2") (pintype "passive"))
    )
    (net (code "112") (name "Net-(IC3A-OSC_IN)") (class "Default")
      (node (ref "C8") (pin "1") (pinfunction "1_1") (pintype "passive"))
      (node (ref "IC3") (pin "5") (pinfunction "OSC_IN_5") (pintype "bidirectional"))
      (node (ref "X2") (pin "1") (pinfunction "1_1") (pintype "passive"))
    )
    (net (code "113") (name "Net-(IC3A-OSC_OUT)") (class "Default")
      (node (ref "C9") (pin "1") (pinfunction "1_1") (pintype "passive"))
      (node (ref "IC3") (pin "6") (pinfunction "OSC_OUT_6") (pintype "bidirectional"))
      (node (ref "X2") (pin "3") (pinfunction "2_3") (pintype "passive"))
    )
    (net (code "114") (name "Net-(U1-DIR)") (class "Default")
      (node (ref "R14") (pin "2") (pinfunction "2_2") (pintype "passive"))
      (node (ref "U1") (pin "11") (pinfunction "DIR_11") (pintype "output"))
    )
    (net (code "115") (name "Net-(U1-ID)") (class "Default")
      (node (ref "R15") (pin "2") (pinfunction "2_2") (pintype "passive"))
      (node (ref "U1") (pin "27") (pinfunction "ID_27") (pintype "output"))
    )
    (net (code "116") (name "Net-(U1-PORT)") (class "Default")
      (node (ref "R13") (pin "2") (pinfunction "2_2") (pintype "passive"))
      (node (ref "U1") (pin "4") (pinfunction "PORT_4") (pintype "input"))
    )
    (net (code "117") (name "Net-(U1-VBUS_DET)") (class "Default")
      (node (ref "R12") (pin "1") (pinfunction "1_1") (pintype "passive"))
      (node (ref "U1") (pin "5") (pinfunction "VBUS_DET_5") (pintype "input"))
    )
    (net (code "118") (name "Net-(U1-~{ENN_CC})") (class "Default")
      (node (ref "R17") (pin "1") (pinfunction "1_1") (pintype "passive"))
      (node (ref "U1") (pin "29") (pinfunction "~{ENN_CC}_29") (pintype "input"))
    )
    (net (code "119") (name "Net-(U1-~{INT_N}{slash}OUT3)") (class "Default")
      (node (ref "R16") (pin "2") (pinfunction "2_2") (pintype "passive"))
      (node (ref "U1") (pin "23") (pinfunction "~{INT_N}/OUT3_23") (pintype "output"))
    )
    (net (code "120") (name "Net-(U2-GRSTZ)") (class "Default")
      (node (ref "C38") (pin "1") (pinfunction "1_1") (pintype "passive"))
      (node (ref "U2") (pin "11") (pinfunction "GRSTZ_11") (pintype "bidirectional"))
    )
    (net (code "121") (name "Net-(U2-TEST)") (class "Default")
      (node (ref "R18") (pin "2") (pinfunction "2_2") (pintype "passive"))
      (node (ref "U2") (pin "10") (pinfunction "TEST_10") (pintype "bidirectional"))
    )
    (net (code "122") (name "Net-(U2-USB_R1)") (class "Default")
      (node (ref "R23") (pin "2") (pinfunction "2_2") (pintype "passive"))
      (node (ref "U2") (pin "24") (pinfunction "USB_R1_24") (pintype "bidirectional"))
    )
    (net (code "123") (name "Net-(U2-USB_VBUS)") (class "Default")
      (node (ref "R21") (pin "1") (pinfunction "1_1") (pintype "passive"))
      (node (ref "R22") (pin "2") (pinfunction "2_2") (pintype "passive"))
      (node (ref "U2") (pin "9") (pinfunction "USB_VBUS_9") (pintype "power_in"))
    )
    (net (code "124") (name "Net-(U2-XI)") (class "Default")
      (node (ref "C36") (pin "1") (pinfunction "1_1") (pintype "passive"))
      (node (ref "U2") (pin "38") (pinfunction "XI_38") (pintype "bidirectional"))
      (node (ref "X3") (pin "1") (pinfunction "1_1") (pintype "passive"))
    )
    (net (code "125") (name "Net-(U2-XO)") (class "Default")
      (node (ref "C37") (pin "1") (pinfunction "1_1") (pintype "passive"))
      (node (ref "U2") (pin "39") (pinfunction "XO_39") (pintype "bidirectional"))
      (node (ref "X3") (pin "3") (pinfunction "2_3") (pintype "passive"))
    )
    (net (code "126") (name "Net-(U3-RREF)") (class "Default")
      (node (ref "R6") (pin "2") (pinfunction "2_2") (pintype "passive"))
      (node (ref "U3") (pin "21") (pinfunction "RREF_21") (pintype "bidirectional"))
    )
    (net (code "127") (name "Net-(U3-XI)") (class "Default")
      (node (ref "C14") (pin "1") (pinfunction "1_1") (pintype "passive"))
      (node (ref "U3") (pin "16") (pinfunction "XI_16") (pintype "bidirectional"))
      (node (ref "X1") (pin "1") (pinfunction "1_1") (pintype "passive"))
    )
    (net (code "128") (name "Net-(U3-XO)") (class "Default")
      (node (ref "C15") (pin "1") (pinfunction "1_1") (pintype "passive"))
      (node (ref "U3") (pin "17") (pinfunction "XO_17") (pintype "bidirectional"))
      (node (ref "X1") (pin "3") (pinfunction "2_3") (pintype "passive"))
    )
    (net (code "129") (name "Net-(U4-VPP_2V5)") (class "Default")
      (node (ref "D4") (pin "C") (pinfunction "C_C") (pintype "passive"))
      (node (ref "U4") (pin "75") (pinfunction "VPP_2V5_75") (pintype "power_in"))
    )
    (net (code "130") (name "Net-(U7-BOOT1)") (class "Default")
      (node (ref "C18") (pin "2") (pinfunction "2_2") (pintype "passive"))
      (node (ref "U7") (pin "2") (pinfunction "BOOT1_2") (pintype "bidirectional"))
    )
    (net (code "131") (name "Net-(U7-BOOT2)") (class "Default")
      (node (ref "C24") (pin "2") (pinfunction "2_2") (pintype "passive"))
      (node (ref "U7") (pin "13") (pinfunction "BOOT2_13") (pintype "bidirectional"))
    )
    (net (code "132") (name "Net-(U7-BP)") (class "Default")
      (node (ref "C30") (pin "1") (pinfunction "1_1") (pintype "passive"))
      (node (ref "U7") (pin "11") (pinfunction "BP_11") (pintype "bidirectional"))
    )
    (net (code "133") (name "Net-(U7-FB1)") (class "Default")
      (node (ref "C23") (pin "2") (pinfunction "2_2") (pintype "passive"))
      (node (ref "R2") (pin "1") (pinfunction "1_1") (pintype "passive"))
      (node (ref "U7") (pin "7") (pinfunction "FB1_7") (pintype "bidirectional"))
    )
    (net (code "134") (name "Net-(U7-FB2)") (class "Default")
      (node (ref "C29") (pin "2") (pinfunction "2_2") (pintype "passive"))
      (node (ref "R4") (pin "1") (pinfunction "1_1") (pintype "passive"))
      (node (ref "U7") (pin "8") (pinfunction "FB2_8") (pintype "bidirectional"))
    )
    (net (code "135") (name "Net-(U7-SW1)") (class "Default")
      (node (ref "C18") (pin "1") (pinfunction "1_1") (pintype "passive"))
      (node (ref "C19") (pin "1") (pinfunction "1_1") (pintype "passive"))
      (node (ref "D6") (pin "C") (pinfunction "C_C") (pintype "passive"))
      (node (ref "L3") (pin "1") (pinfunction "1_1") (pintype "passive"))
      (node (ref "U7") (pin "3") (pinfunction "SW1_3") (pintype "bidirectional"))
    )
    (net (code "136") (name "Net-(U7-SW2)") (class "Default")
      (node (ref "C24") (pin "1") (pinfunction "1_1") (pintype "passive"))
      (node (ref "C25") (pin "1") (pinfunction "1_1") (pintype "passive"))
      (node (ref "D7") (pin "C") (pinfunction "C_C") (pintype "passive"))
      (node (ref "L4") (pin "1") (pinfunction "1_1") (pintype "passive"))
      (node (ref "U7") (pin "12") (pinfunction "SW2_12") (pintype "bidirectional"))
    )
    (net (code "137") (name "SBU1") (class "Default")
      (node (ref "D3") (pin "7") (pinfunction "D3N_7") (pintype "bidirectional"))
      (node (ref "D3") (pin "8") (pinfunction "D3N_8") (pintype "bidirectional"))
      (node (ref "J2") (pin "A8") (pinfunction "SBU1_A8") (pintype "passive"))
    )
    (net (code "138") (name "SBU2") (class "Default")
      (node (ref "D3") (pin "6") (pinfunction "D3P_6") (pintype "bidirectional"))
      (node (ref "D3") (pin "9") (pinfunction "D3P_9") (pintype "bidirectional"))
      (node (ref "J2") (pin "B8") (pinfunction "SBU2_B8") (pintype "passive"))
    )
    (net (code "139") (name "SSRXN1_UP") (class "Default")
      (node (ref "C33") (pin "1") (pinfunction "1_1") (pintype "passive"))
      (node (ref "D1") (pin "1") (pinfunction "D1+_1") (pintype "bidirectional"))
      (node (ref "D1") (pin "10") (pinfunction "D1+_10") (pintype "bidirectional"))
      (node (ref "J2") (pin "B10") (pinfunction "SSRXN1_B10") (pintype "passive"))
    )
    (net (code "140") (name "SSRXN1_UP_C") (class "Default")
      (node (ref "C33") (pin "2") (pinfunction "2_2") (pintype "passive"))
      (node (ref "U1") (pin "14") (pinfunction "RX1N_14") (pintype "bidirectional"))
    )
    (net (code "141") (name "SSRXN2_UP") (class "Default")
      (node (ref "C32") (pin "1") (pinfunction "1_1") (pintype "passive"))
      (node (ref "D2") (pin "1") (pinfunction "D1+_1") (pintype "bidirectional"))
      (node (ref "D2") (pin "10") (pinfunction "D1+_10") (pintype "bidirectional"))
      (node (ref "J2") (pin "A10") (pinfunction "SSRXN2_A10") (pintype "passive"))
    )
    (net (code "142") (name "SSRXN2_UP_C") (class "Default")
      (node (ref "C32") (pin "2") (pinfunction "2_2") (pintype "passive"))
      (node (ref "U1") (pin "18") (pinfunction "RX2N_18") (pintype "bidirectional"))
    )
    (net (code "143") (name "SSRXN_UP") (class "Default")
      (node (ref "U1") (pin "10") (pinfunction "RXN_10") (pintype "bidirectional"))
      (node (ref "U2") (pin "31") (pinfunction "USB_SSRXM_UP_31") (pintype "bidirectional"))
    )
    (net (code "144") (name "SSRXP1_UP") (class "Default")
      (node (ref "C31") (pin "1") (pinfunction "1_1") (pintype "passive"))
      (node (ref "D1") (pin "2") (pinfunction "D1-_2") (pintype "bidirectional"))
      (node (ref "D1") (pin "9") (pinfunction "D1-_9") (pintype "bidirectional"))
      (node (ref "J2") (pin "B11") (pinfunction "SSRXP1_B11") (pintype "passive"))
    )
    (net (code "145") (name "SSRXP1_UP_C") (class "Default")
      (node (ref "C31") (pin "2") (pinfunction "2_2") (pintype "passive"))
      (node (ref "U1") (pin "15") (pinfunction "RX1P_15") (pintype "bidirectional"))
    )
    (net (code "146") (name "SSRXP2_UP") (class "Default")
      (node (ref "C34") (pin "1") (pinfunction "1_1") (pintype "passive"))
      (node (ref "D2") (pin "2") (pinfunction "D1-_2") (pintype "bidirectional"))
      (node (ref "D2") (pin "9") (pinfunction "D1-_9") (pintype "bidirectional"))
      (node (ref "J2") (pin "A11") (pinfunction "SSRXP2_A11") (pintype "passive"))
    )
    (net (code "147") (name "SSRXP2_UP_C") (class "Default")
      (node (ref "C34") (pin "2") (pinfunction "2_2") (pintype "passive"))
      (node (ref "U1") (pin "19") (pinfunction "RX2P_19") (pintype "bidirectional"))
    )
    (net (code "148") (name "SSRXP_UP") (class "Default")
      (node (ref "U1") (pin "9") (pinfunction "RXP_9") (pintype "bidirectional"))
      (node (ref "U2") (pin "32") (pinfunction "USB_SSRXP_UP_32") (pintype "bidirectional"))
    )
    (net (code "149") (name "SSTXN1_UP") (class "Default")
      (node (ref "D1") (pin "5") (pinfunction "D2-_5") (pintype "bidirectional"))
      (node (ref "D1") (pin "6") (pinfunction "D2-_6") (pintype "bidirectional"))
      (node (ref "J2") (pin "A3") (pinfunction "SSTXN1_A3") (pintype "passive"))
      (node (ref "U1") (pin "16") (pinfunction "TX1N_16") (pintype "bidirectional"))
    )
    (net (code "150") (name "SSTXN2_UP") (class "Default")
      (node (ref "D2") (pin "4") (pinfunction "D2+_4") (pintype "bidirectional"))
      (node (ref "D2") (pin "7") (pinfunction "D2+_7") (pintype "bidirectional"))
      (node (ref "J2") (pin "B3") (pinfunction "SSTXN2_B3") (pintype "passive"))
      (node (ref "U1") (pin "20") (pinfunction "TX2N_20") (pintype "bidirectional"))
    )
    (net (code "151") (name "SSTXN_UP") (class "Default")
      (node (ref "U1") (pin "7") (pinfunction "TXN_7") (pintype "bidirectional"))
      (node (ref "U2") (pin "28") (pinfunction "USB_SSTXM_UP_28") (pintype "bidirectional"))
    )
    (net (code "152") (name "SSTXP1_UP") (class "Default")
      (node (ref "D1") (pin "4") (pinfunction "D2+_4") (pintype "bidirectional"))
      (node (ref "D1") (pin "7") (pinfunction "D2+_7") (pintype "bidirectional"))
      (node (ref "J2") (pin "A2") (pinfunction "SSTXP1_A2") (pintype "passive"))
      (node (ref "U1") (pin "17") (pinfunction "TX1P_17") (pintype "bidirectional"))
    )
    (net (code "153") (name "SSTXP2_UP") (class "Default")
      (node (ref "D2") (pin "5") (pinfunction "D2-_5") (pintype "bidirectional"))
      (node (ref "D2") (pin "6") (pinfunction "D2-_6") (pintype "bidirectional"))
      (node (ref "J2") (pin "B2") (pinfunction "SSTXP2_B2") (pintype "passive"))
      (node (ref "U1") (pin "21") (pinfunction "TX2P_21") (pintype "bidirectional"))
    )
    (net (code "154") (name "SSTXP_UP") (class "Default")
      (node (ref "U1") (pin "6") (pinfunction "TXP_6") (pintype "bidirectional"))
      (node (ref "U2") (pin "29") (pinfunction "USB_SSTXP_UP_29") (pintype "bidirectional"))
    )
    (net (code "155") (name "VCCINT") (class "Default")
      (node (ref "C26") (pin "1") (pinfunction "1_1") (pintype "passive"))
      (node (ref "C27") (pin "1") (pinfunction "1_1") (pintype "passive"))
      (node (ref "C28") (pin "1") (pinfunction "1_1") (pintype "passive"))
      (node (ref "C29") (pin "1") (pinfunction "1_1") (pintype "passive"))
      (node (ref "C650") (pin "1") (pinfunction "1_1") (pintype "passive"))
      (node (ref "C651") (pin "1") (pinfunction "1_1") (pintype "passive"))
      (node (ref "C652") (pin "1") (pinfunction "1_1") (pintype "passive"))
      (node (ref "C653") (pin "1") (pinfunction "1_1") (pintype "passive"))
      (node (ref "C654") (pin "1") (pinfunction "1_1") (pintype "passive"))
      (node (ref "C655") (pin "1") (pinfunction "1_1") (pintype "passive"))
      (node (ref "C656") (pin "1") (pinfunction "1_1") (pintype "passive"))
      (node (ref "L4") (pin "2") (pinfunction "2_2") (pintype "passive"))
      (node (ref "R4") (pin "2") (pinfunction "2_2") (pintype "passive"))
      (node (ref "U2") (pin "1") (pinfunction "VDD_1") (pintype "power_in"))
      (node (ref "U2") (pin "12") (pinfunction "VDD_12") (pintype "bidirectional"))
      (node (ref "U2") (pin "30") (pinfunction "VDD_30") (pintype "bidirectional"))
      (node (ref "U2") (pin "34") (pinfunction "VDD_34") (pintype "bidirectional"))
      (node (ref "U2") (pin "45") (pinfunction "VDD_45") (pintype "bidirectional"))
      (node (ref "U4") (pin "11") (pinfunction "VCC_11") (pintype "power_in"))
      (node (ref "U4") (pin "35") (pinfunction "VCC_35") (pintype "power_in"))
      (node (ref "U4") (pin "61") (pinfunction "VCC_61") (pintype "power_in"))
      (node (ref "U4") (pin "77") (pinfunction "VCC_77") (pintype "power_in"))
    )
    (net (code "156") (name "VPP_FAST") (class "Default")
      (node (ref "U4") (pin "76") (pinfunction "VPP_FAST_76") (pintype "power_in"))
    )
    (net (code "157") (name "V_USB") (class "Default")
      (node (ref "C11") (pin "1") (pinfunction "1_1") (pintype "passive"))
      (node (ref "C12") (pin "1") (pinfunction "1_1") (pintype "passive"))
      (node (ref "C35") (pin "1") (pinfunction "1_1") (pintype "passive"))
      (node (ref "J2") (pin "A4") (pinfunction "VBUS_A4") (pintype "passive"))
      (node (ref "J2") (pin "A9") (pinfunction "VBUS_A9") (pintype "passive"))
      (node (ref "J2") (pin "B4") (pinfunction "VBUS_B4") (pintype "passive"))
      (node (ref "J2") (pin "B9") (pinfunction "VBUS_B9") (pintype "passive"))
      (node (ref "R12") (pin "2") (pinfunction "2_2") (pintype "passive"))
      (node (ref "R14") (pin "1") (pinfunction "1_1") (pintype "passive"))
      (node (ref "R15") (pin "1") (pinfunction "1_1") (pintype "passive"))
      (node (ref "R16") (pin "1") (pinfunction "1_1") (pintype "passive"))
      (node (ref "R21") (pin "2") (pinfunction "2_2") (pintype "passive"))
      (node (ref "R9") (pin "2") (pinfunction "2_2") (pintype "passive"))
      (node (ref "U$4") (pin "P$23") (pinfunction "23_P$23") (pintype "passive"))
      (node (ref "U$4") (pin "P$24") (pinfunction "24_P$24") (pintype "passive"))
      (node (ref "U1") (pin "30") (pinfunction "VDD5_30") (pintype "power_in"))
      (node (ref "U7") (pin "1") (pinfunction "PVDD1_1") (pintype "bidirectional"))
      (node (ref "U7") (pin "14") (pinfunction "PVDD2_14") (pintype "bidirectional"))
    )
    (net (code "158") (name "unconnected-(IC3A-PA0-WKUP-Pad10)") (class "Default")
      (node (ref "IC3") (pin "10") (pinfunction "PA0-WKUP_10") (pintype "bidirectional"))
    )
    (net (code "159") (name "unconnected-(IC3A-PA1-Pad11)") (class "Default")
      (node (ref "IC3") (pin "11") (pinfunction "PA1_11") (pintype "bidirectional"))
    )
    (net (code "160") (name "unconnected-(IC3A-PA4-Pad14)") (class "Default")
      (node (ref "IC3") (pin "14") (pinfunction "PA4_14") (pintype "bidirectional"))
    )
    (net (code "161") (name "unconnected-(IC3A-PA5-Pad15)") (class "Default")
      (node (ref "IC3") (pin "15") (pinfunction "PA5_15") (pintype "bidirectional"))
    )
    (net (code "162") (name "unconnected-(IC3A-PA6-Pad16)") (class "Default")
      (node (ref "IC3") (pin "16") (pinfunction "PA6_16") (pintype "bidirectional"))
    )
    (net (code "163") (name "unconnected-(IC3A-PA8-Pad29)") (class "Default")
      (node (ref "IC3") (pin "29") (pinfunction "PA8_29") (pintype "bidirectional"))
    )
    (net (code "164") (name "unconnected-(IC3A-PA9-Pad30)") (class "Default")
      (node (ref "IC3") (pin "30") (pinfunction "PA9_30") (pintype "bidirectional"))
    )
    (net (code "165") (name "unconnected-(IC3A-PA15-Pad38)") (class "Default")
      (node (ref "IC3") (pin "38") (pinfunction "PA15_38") (pintype "bidirectional"))
    )
    (net (code "166") (name "unconnected-(IC3A-PB1-Pad19)") (class "Default")
      (node (ref "IC3") (pin "19") (pinfunction "PB1_19") (pintype "bidirectional"))
    )
    (net (code "167") (name "unconnected-(IC3A-PB9-Pad46)") (class "Default")
      (node (ref "IC3") (pin "46") (pinfunction "PB9_46") (pintype "bidirectional"))
    )
    (net (code "168") (name "unconnected-(IC3A-PB10-Pad21)") (class "Default")
      (node (ref "IC3") (pin "21") (pinfunction "PB10_21") (pintype "bidirectional"))
    )
    (net (code "169") (name "unconnected-(IC3A-PB11-Pad22)") (class "Default")
      (node (ref "IC3") (pin "22") (pinfunction "PB11_22") (pintype "bidirectional"))
    )
    (net (code "170") (name "unconnected-(IC3A-PB15-Pad28)") (class "Default")
      (node (ref "IC3") (pin "28") (pinfunction "PB15_28") (pintype "bidirectional"))
    )
    (net (code "171") (name "unconnected-(IC3A-PC13-Pad2)") (class "Default")
      (node (ref "IC3") (pin "2") (pinfunction "PC13_2") (pintype "bidirectional"))
    )
    (net (code "172") (name "unconnected-(IC3A-PC14-Pad3)") (class "Default")
      (node (ref "IC3") (pin "3") (pinfunction "PC14_3") (pintype "bidirectional"))
    )
    (net (code "173") (name "unconnected-(IC3A-PC15-Pad4)") (class "Default")
      (node (ref "IC3") (pin "4") (pinfunction "PC15_4") (pintype "bidirectional"))
    )
    (net (code "174") (name "unconnected-(S2-Pad2)") (class "Default")
      (node (ref "S2") (pin "2") (pinfunction "2_2") (pintype "passive"))
    )
    (net (code "175") (name "unconnected-(S2-Pad4)") (class "Default")
      (node (ref "S2") (pin "4") (pinfunction "4_4") (pintype "passive"))
    )
    (net (code "176") (name "unconnected-(U$1-PadA2)") (class "Default")
      (node (ref "U$1") (pin "A2") (pinfunction "A2_A2") (pintype "bidirectional"))
    )
    (net (code "177") (name "unconnected-(U$1-PadA3)") (class "Default")
      (node (ref "U$1") (pin "A3") (pinfunction "A3_A3") (pintype "bidirectional"))
    )
    (net (code "178") (name "unconnected-(U$1-PadA4)") (class "Default")
      (node (ref "U$1") (pin "A4") (pinfunction "A4_A4") (pintype "bidirectional"))
    )
    (net (code "179") (name "unconnected-(U$1-PadA5)") (class "Default")
      (node (ref "U$1") (pin "A5") (pinfunction "A5_A5") (pintype "bidirectional"))
    )
    (net (code "180") (name "unconnected-(U$1-PadA6)") (class "Default")
      (node (ref "U$1") (pin "A6") (pinfunction "A6_A6") (pintype "bidirectional"))
    )
    (net (code "181") (name "unconnected-(U$1-PadA7)") (class "Default")
      (node (ref "U$1") (pin "A7") (pinfunction "A7_A7") (pintype "bidirectional"))
    )
    (net (code "182") (name "unconnected-(U$1-PadA8)") (class "Default")
      (node (ref "U$1") (pin "A8") (pinfunction "A8_A8") (pintype "bidirectional"))
    )
    (net (code "183") (name "unconnected-(U$1-PadA9)") (class "Default")
      (node (ref "U$1") (pin "A9") (pinfunction "A9_A9") (pintype "bidirectional"))
    )
    (net (code "184") (name "unconnected-(U$1-PadA10)") (class "Default")
      (node (ref "U$1") (pin "A10") (pinfunction "A10_A10") (pintype "bidirectional"))
    )
    (net (code "185") (name "unconnected-(U$1-PadA18)") (class "Default")
      (node (ref "U$1") (pin "A18") (pinfunction "A18_A18") (pintype "bidirectional"))
    )
    (net (code "186") (name "unconnected-(U$1-PadB2)") (class "Default")
      (node (ref "U$1") (pin "B2") (pinfunction "B2_B2") (pintype "bidirectional"))
    )
    (net (code "187") (name "unconnected-(U$1-PadB3)") (class "Default")
      (node (ref "U$1") (pin "B3") (pinfunction "B3_B3") (pintype "bidirectional"))
    )
    (net (code "188") (name "unconnected-(U$1-PadB4)") (class "Default")
      (node (ref "U$1") (pin "B4") (pinfunction "B4_B4") (pintype "bidirectional"))
    )
    (net (code "189") (name "unconnected-(U$1-PadB5)") (class "Default")
      (node (ref "U$1") (pin "B5") (pinfunction "B5_B5") (pintype "bidirectional"))
    )
    (net (code "190") (name "unconnected-(U$1-PadB6)") (class "Default")
      (node (ref "U$1") (pin "B6") (pinfunction "B6_B6") (pintype "bidirectional"))
    )
    (net (code "191") (name "unconnected-(U$1-PadB7)") (class "Default")
      (node (ref "U$1") (pin "B7") (pinfunction "B7_B7") (pintype "bidirectional"))
    )
    (net (code "192") (name "unconnected-(U$1-PadB14)") (class "Default")
      (node (ref "U$1") (pin "B14") (pinfunction "B14_B14") (pintype "bidirectional"))
    )
    (net (code "193") (name "unconnected-(U$1-PadB15)") (class "Default")
      (node (ref "U$1") (pin "B15") (pinfunction "B15_B15") (pintype "bidirectional"))
    )
    (net (code "194") (name "unconnected-(U$1-PadB18)") (class "Default")
      (node (ref "U$1") (pin "B18") (pinfunction "B18_B18") (pintype "bidirectional"))
    )
    (net (code "195") (name "unconnected-(U$2-RTCK-Pad7)") (class "Default")
      (node (ref "U$2") (pin "7") (pinfunction "RTCK_7") (pintype "bidirectional"))
    )
    (net (code "196") (name "unconnected-(U$2-TDI-Pad8)") (class "Default")
      (node (ref "U$2") (pin "8") (pinfunction "TDI_8") (pintype "bidirectional"))
    )
    (net (code "197") (name "unconnected-(U$2-TDO-Pad6)") (class "Default")
      (node (ref "U$2") (pin "6") (pinfunction "TDO_6") (pintype "bidirectional"))
    )
    (net (code "198") (name "unconnected-(U1-ADDR-Pad22)") (class "Default")
      (node (ref "U1") (pin "22") (pinfunction "ADDR_22") (pintype "input"))
    )
    (net (code "199") (name "unconnected-(U1-CURRENT_MODE-Pad3)") (class "Default")
      (node (ref "U1") (pin "3") (pinfunction "CURRENT_MODE_3") (pintype "input"))
    )
    (net (code "200") (name "unconnected-(U1-SCL{slash}OUT2-Pad26)") (class "Default")
      (node (ref "U1") (pin "26") (pinfunction "SCL/OUT2_26") (pintype "bidirectional"))
    )
    (net (code "201") (name "unconnected-(U1-SDA{slash}OUT1-Pad25)") (class "Default")
      (node (ref "U1") (pin "25") (pinfunction "SDA/OUT1_25") (pintype "bidirectional"))
    )
    (net (code "202") (name "unconnected-(U1-VCONN_FAULT_N-Pad24)") (class "Default")
      (node (ref "U1") (pin "24") (pinfunction "VCONN_FAULT_N_24") (pintype "output"))
    )
    (net (code "203") (name "unconnected-(U2-FULLPWRMGMTZ{slash}SMBA1{slash}SS_UP-Pad36)") (class "Default")
      (node (ref "U2") (pin "36") (pinfunction "FULLPWRMGMTZ/SMBA1/SS_UP_36") (pintype "bidirectional"))
    )
    (net (code "204") (name "unconnected-(U2-GANGED{slash}SMBA2{slash}HS_UP-Pad35)") (class "Default")
      (node (ref "U2") (pin "35") (pinfunction "GANGED/SMBA2/HS_UP_35") (pintype "bidirectional"))
    )
    (net (code "205") (name "unconnected-(U2-OVERCUR1Z-Pad5)") (class "Default")
      (node (ref "U2") (pin "5") (pinfunction "OVERCUR1Z_5") (pintype "bidirectional"))
    )
    (net (code "206") (name "unconnected-(U2-OVERCUR2Z-Pad8)") (class "Default")
      (node (ref "U2") (pin "8") (pinfunction "OVERCUR2Z_8") (pintype "bidirectional"))
    )
    (net (code "207") (name "unconnected-(U2-PWRCTL1{slash}BATEN1-Pad4)") (class "Default")
      (node (ref "U2") (pin "4") (pinfunction "PWRCTL1/BATEN1_4") (pintype "bidirectional"))
    )
    (net (code "208") (name "unconnected-(U2-PWRCTL2{slash}BATEN2-Pad6)") (class "Default")
      (node (ref "U2") (pin "6") (pinfunction "PWRCTL2/BATEN2_6") (pintype "bidirectional"))
    )
    (net (code "209") (name "unconnected-(U2-PWRCTL_POL{slash}SS_DN1-Pad21)") (class "Default")
      (node (ref "U2") (pin "21") (pinfunction "PWRCTL_POL/SS_DN1_21") (pintype "bidirectional"))
    )
    (net (code "210") (name "unconnected-(U2-SCL{slash}SMBCLK-Pad2)") (class "Default")
      (node (ref "U2") (pin "2") (pinfunction "SCL/SMBCLK_2") (pintype "bidirectional"))
    )
    (net (code "211") (name "unconnected-(U2-SDA{slash}SMBDAT-Pad3)") (class "Default")
      (node (ref "U2") (pin "3") (pinfunction "SDA/SMBDAT_3") (pintype "bidirectional"))
    )
    (net (code "212") (name "unconnected-(U2-SMBUSZ{slash}SS_DN2-Pad22)") (class "Default")
      (node (ref "U2") (pin "22") (pinfunction "SMBUSZ/SS_DN2_22") (pintype "bidirectional"))
    )
    (net (code "213") (name "unconnected-(U2-USB_SSRXM_DN1-Pad47)") (class "Default")
      (node (ref "U2") (pin "47") (pinfunction "USB_SSRXM_DN1_47") (pintype "bidirectional"))
    )
    (net (code "214") (name "unconnected-(U2-USB_SSRXP_DN1-Pad46)") (class "Default")
      (node (ref "U2") (pin "46") (pinfunction "USB_SSRXP_DN1_46") (pintype "bidirectional"))
    )
    (net (code "215") (name "unconnected-(U2-USB_SSTXM_DN1-Pad44)") (class "Default")
      (node (ref "U2") (pin "44") (pinfunction "USB_SSTXM_DN1_44") (pintype "bidirectional"))
    )
    (net (code "216") (name "unconnected-(U2-USB_SSTXP_DN1-Pad43)") (class "Default")
      (node (ref "U2") (pin "43") (pinfunction "USB_SSTXP_DN1_43") (pintype "bidirectional"))
    )
    (net (code "217") (name "unconnected-(U3-~{WAKEUP}-Pad11)") (class "Default")
      (node (ref "U3") (pin "11") (pinfunction "~{WAKEUP}_11") (pintype "bidirectional"))
    )
    (net (code "218") (name "unconnected-(U4-IOB_43_CBSEL1-Pad42)") (class "Default")
      (node (ref "U4") (pin "42") (pinfunction "IOB_43_CBSEL1_42") (pintype "bidirectional"))
    )
    (net (code "219") (name "unconnected-(U5-HOLD-Pad7)") (class "Default")
      (node (ref "U5") (pin "7") (pinfunction "HOLD_7") (pintype "bidirectional"))
    )
    (net (code "220") (name "unconnected-(U5-WP-Pad3)") (class "Default")
      (node (ref "U5") (pin "3") (pinfunction "WP_3") (pintype "bidirectional"))
    )
  )
)
